# Super_LED_board.net
KiCad netlist of a schematic drawn in EAGLE
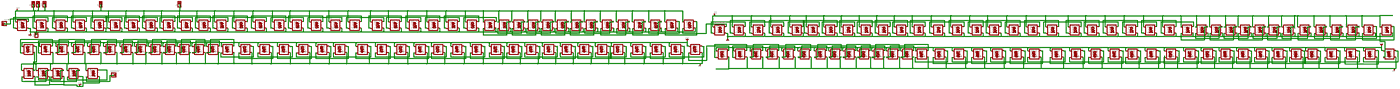
[diagram p0: schematic, sheet 1, overview]
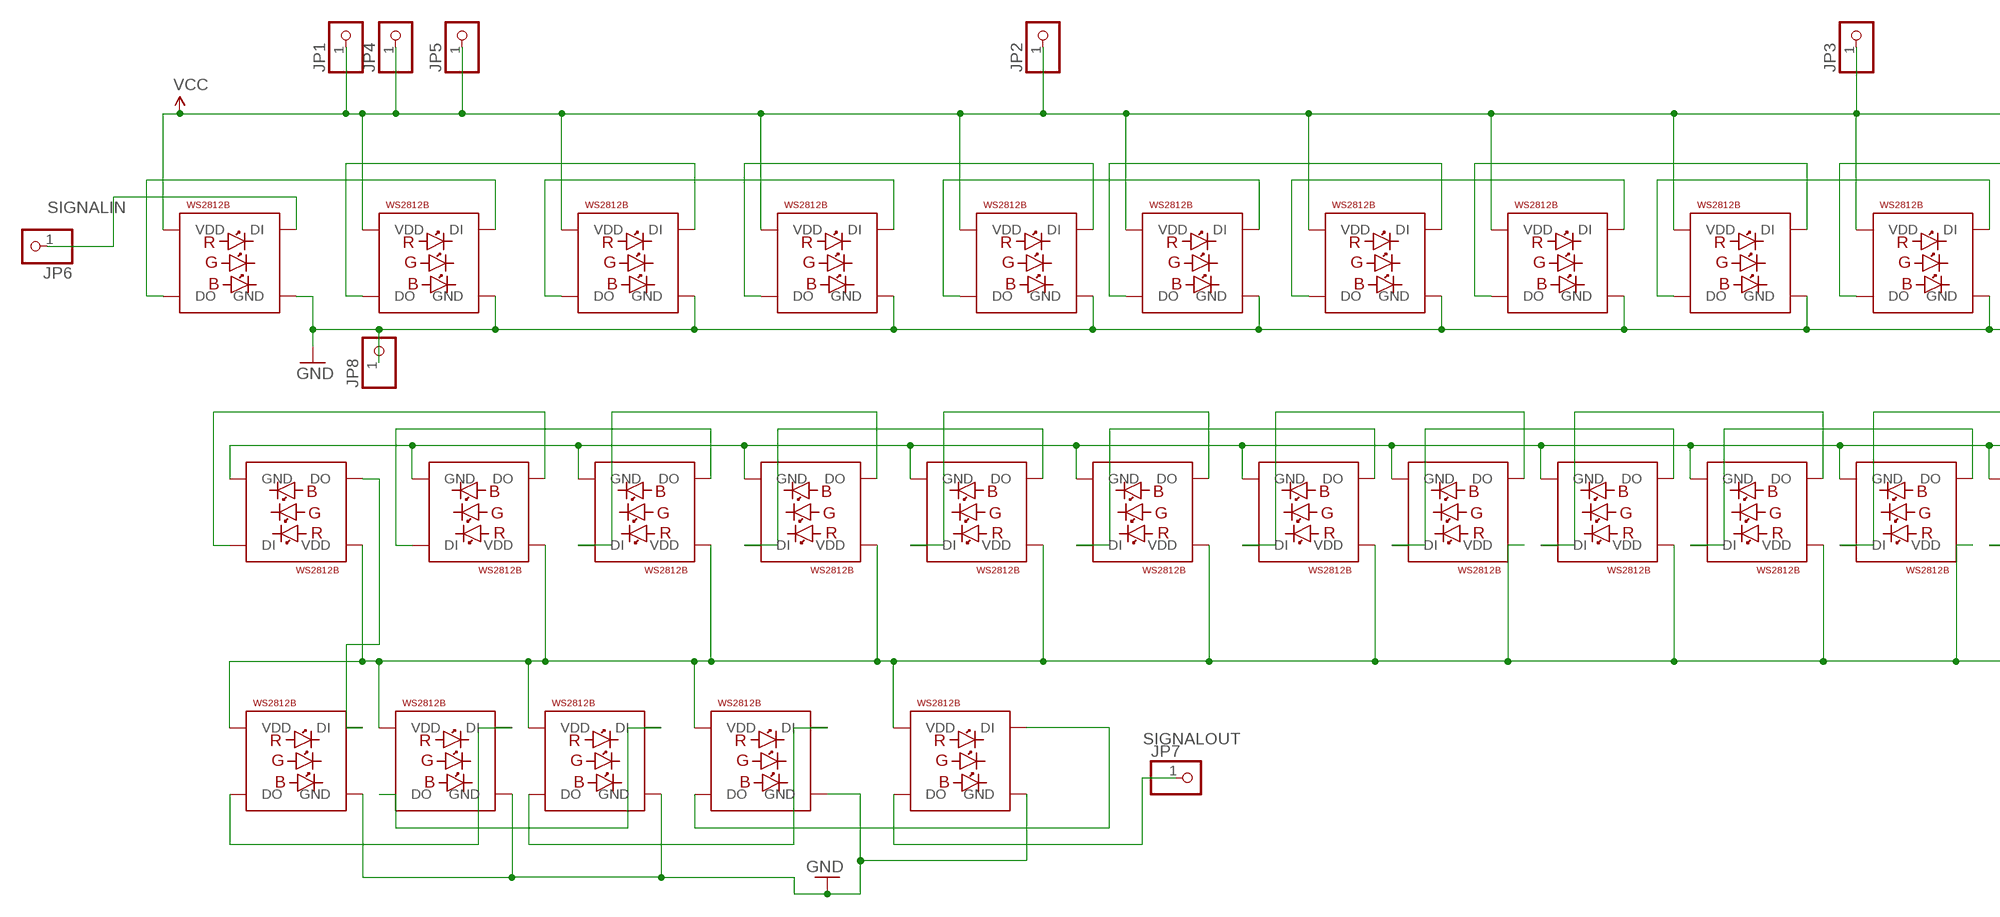
[diagram p1: schematic, sheet 1, part 1 of 8]
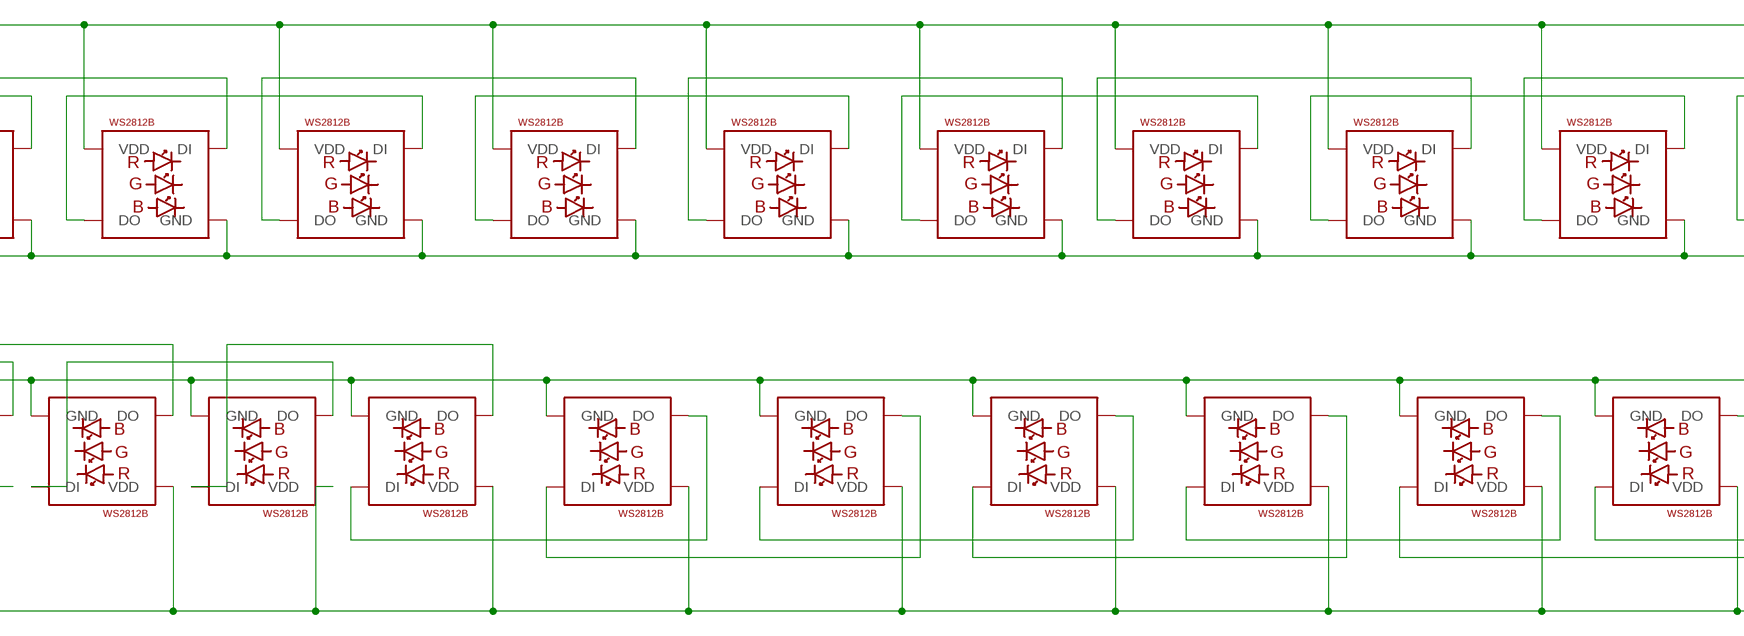
[diagram p2: schematic, sheet 1, part 2 of 8]
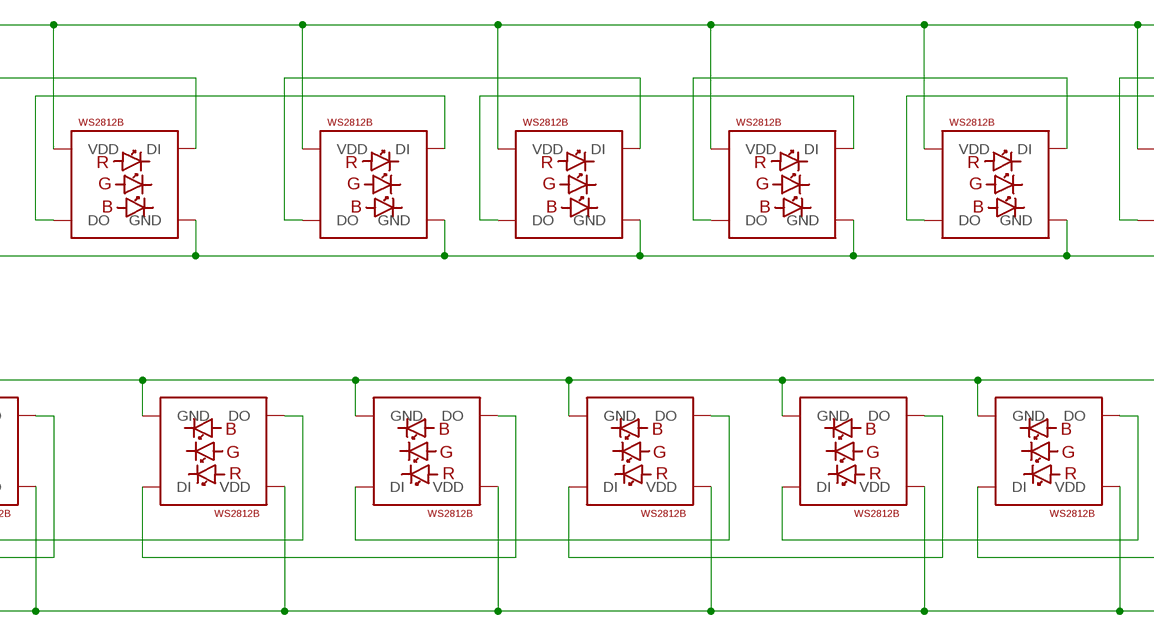
[diagram p3: schematic, sheet 1, part 3 of 8]
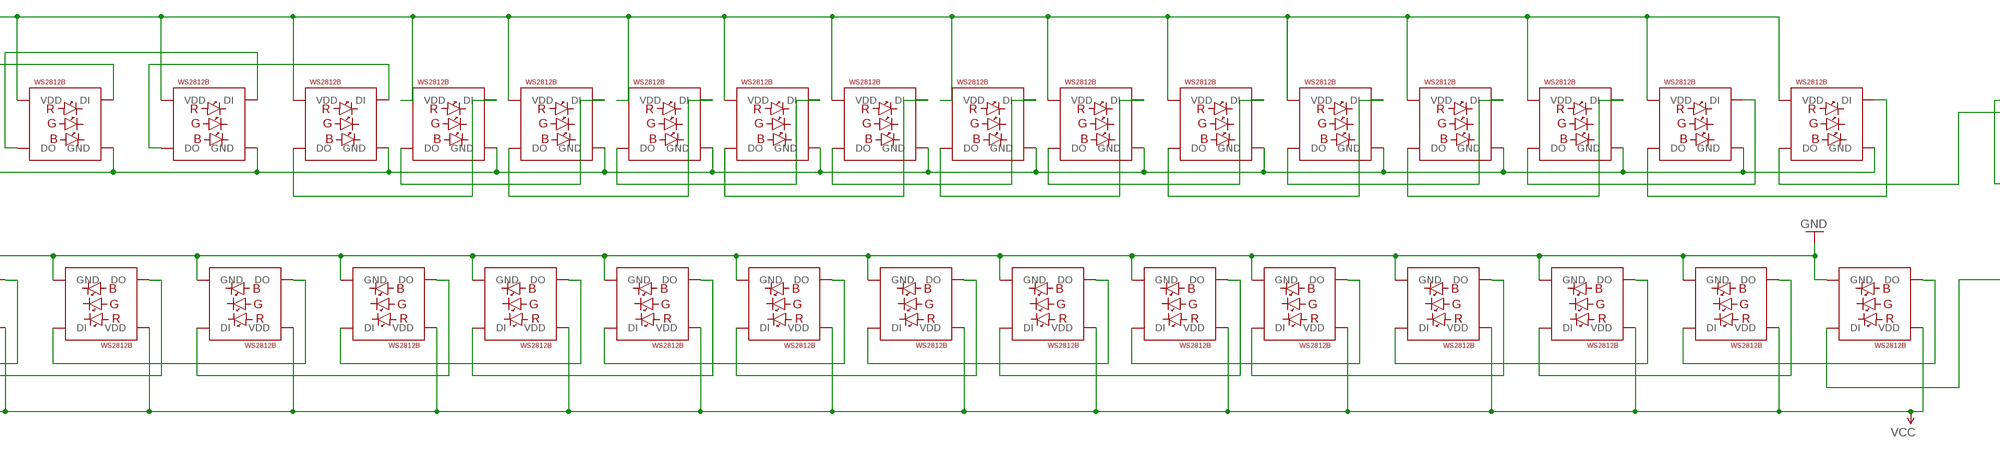
[diagram p4: schematic, sheet 1, part 4 of 8]
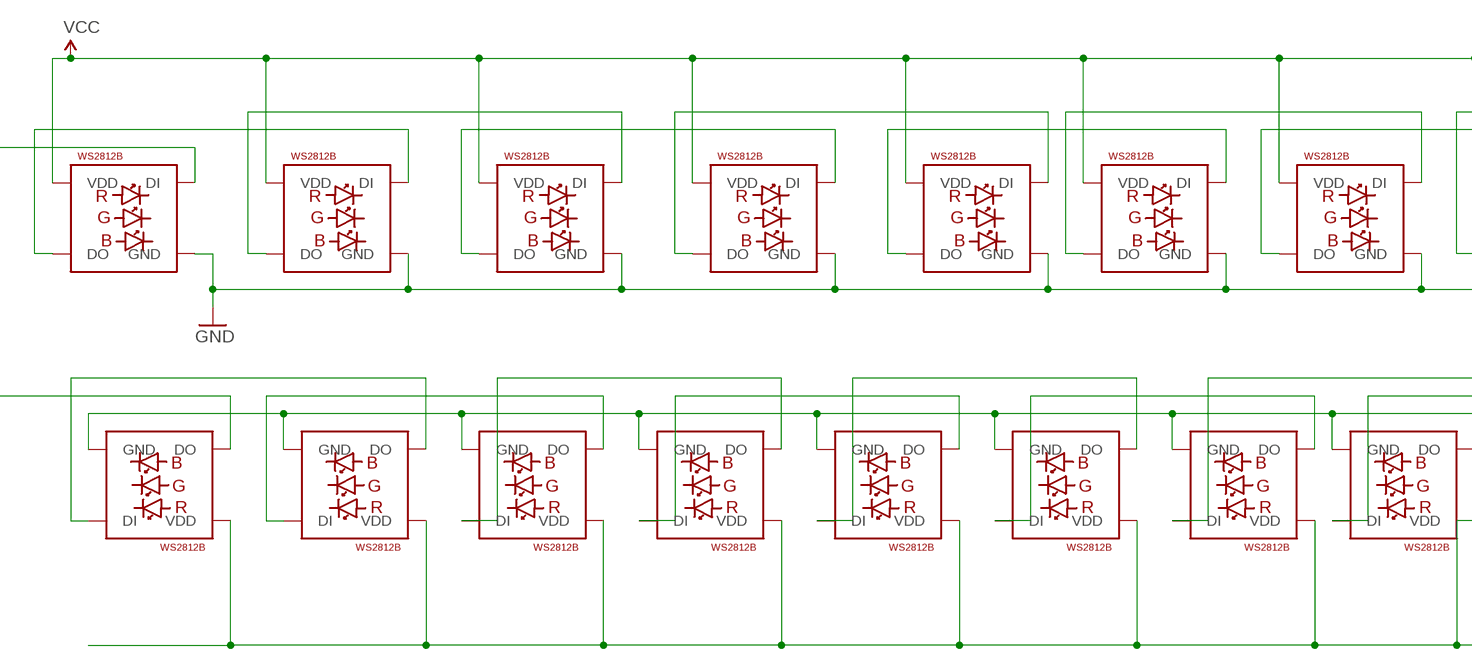
[diagram p5: schematic, sheet 1, part 5 of 8]
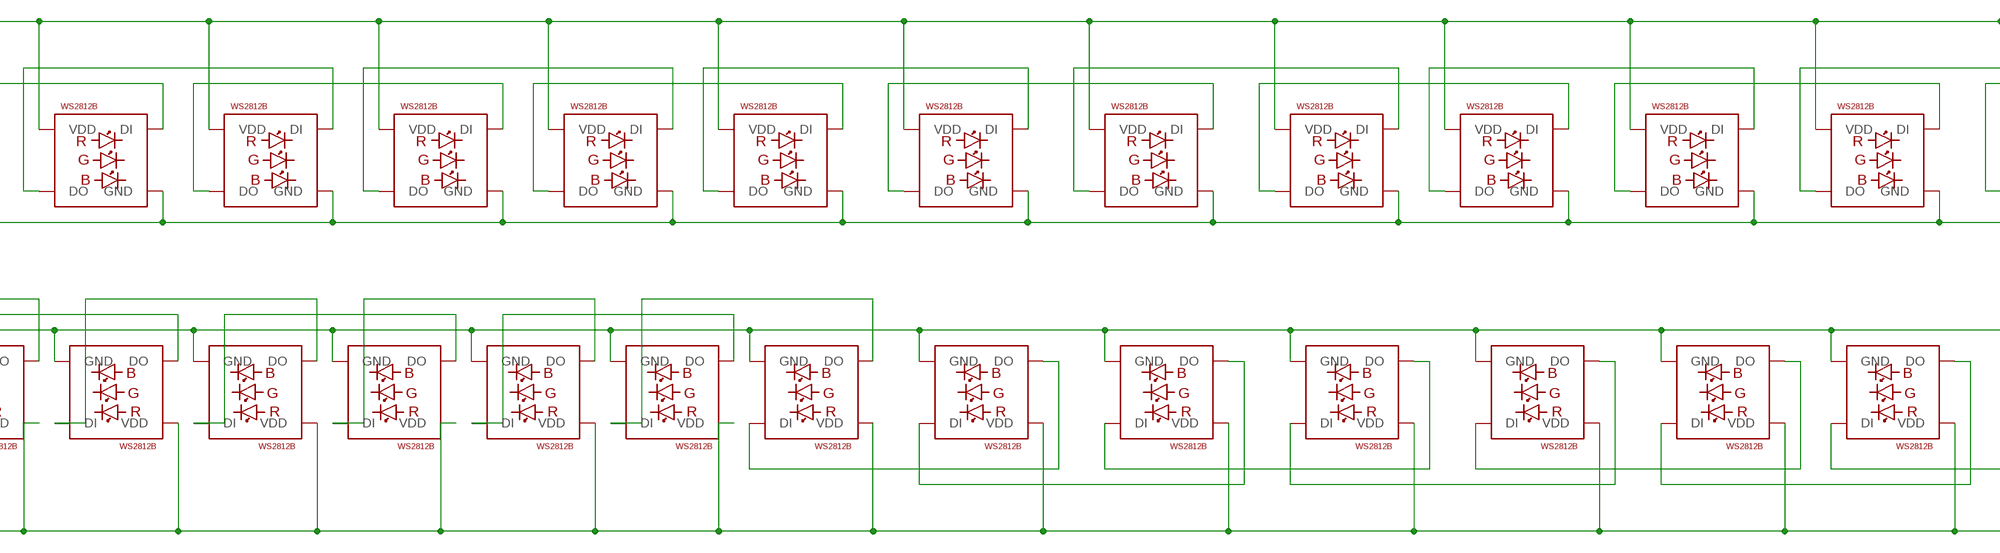
[diagram p6: schematic, sheet 1, part 6 of 8]
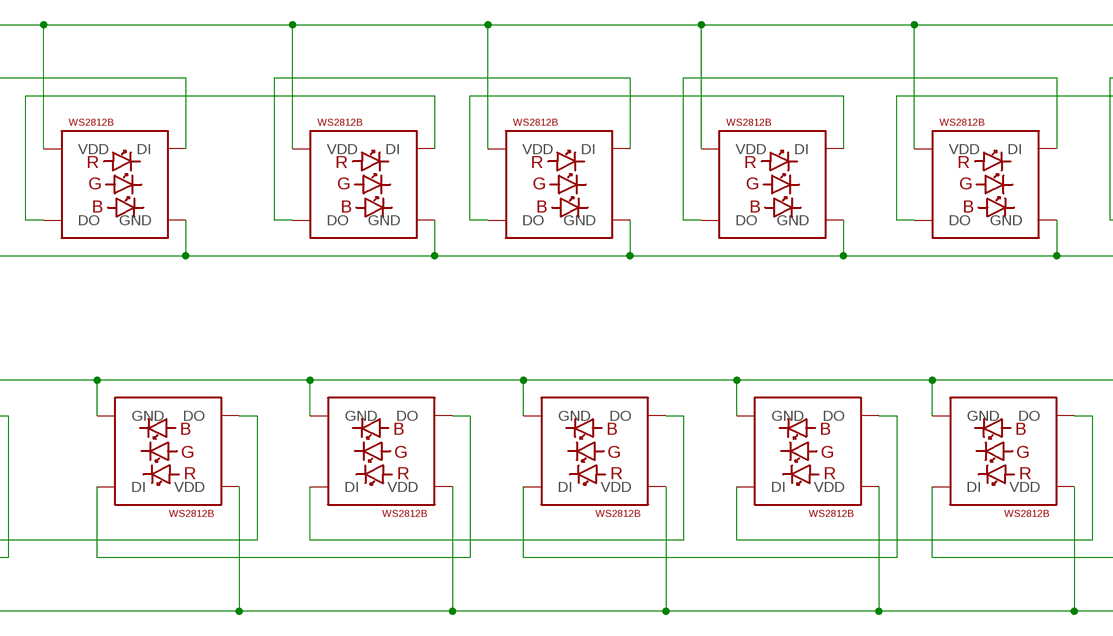
[diagram p7: schematic, sheet 1, part 7 of 8]
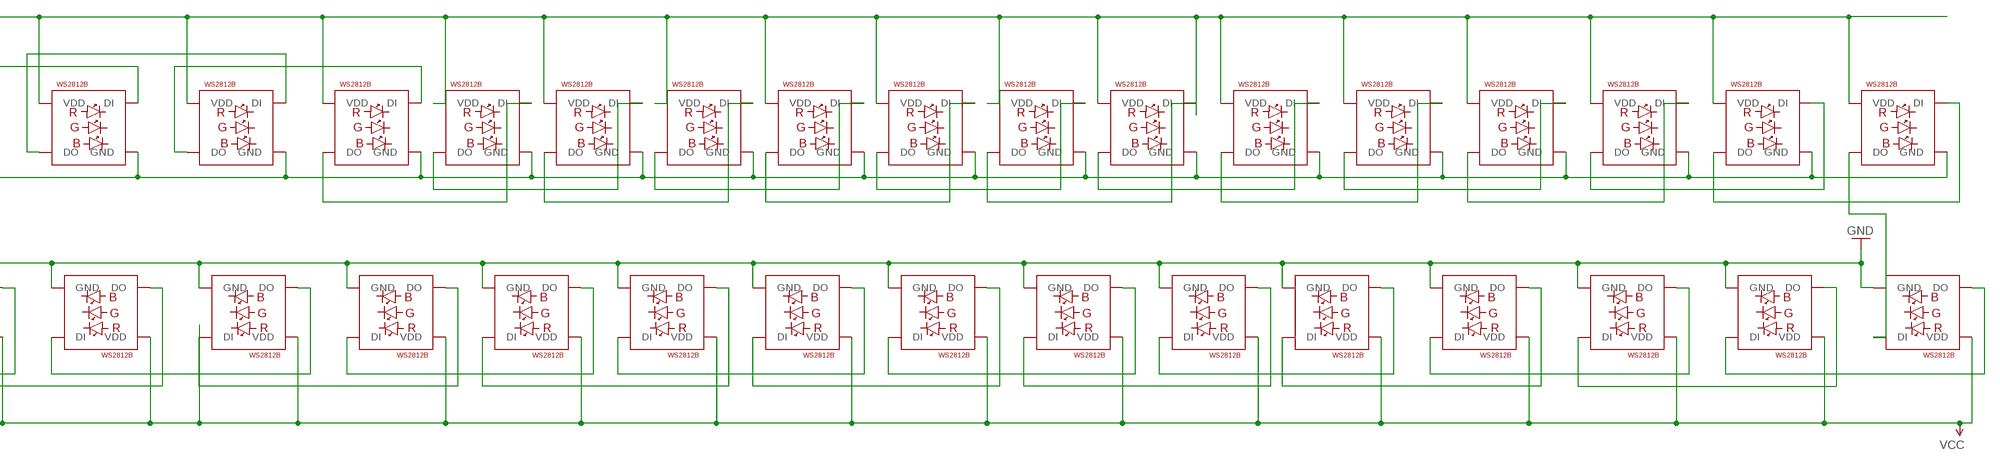
[diagram p8: schematic, sheet 1, part 8 of 8]

(export (version "E")
  (design (tool "Eeschema 10.0.6"))
  (components
    (comp (ref "JP1")
      (value "PINHD-1X1")
      (footprint "eagle-import:1X01")
      (libsource (lib "eagle-import") (part "PINHD-1X1"))
    )
    (comp (ref "JP2")
      (value "PINHD-1X1")
      (footprint "eagle-import:1X01")
      (libsource (lib "eagle-import") (part "PINHD-1X1"))
    )
    (comp (ref "JP3")
      (value "PINHD-1X1")
      (footprint "eagle-import:1X01")
      (libsource (lib "eagle-import") (part "PINHD-1X1"))
    )
    (comp (ref "JP4")
      (value "PINHD-1X1")
      (footprint "eagle-import:1X01")
      (libsource (lib "eagle-import") (part "PINHD-1X1"))
    )
    (comp (ref "JP5")
      (value "PINHD-1X1")
      (footprint "eagle-import:1X01")
      (libsource (lib "eagle-import") (part "PINHD-1X1"))
    )
    (comp (ref "JP6")
      (value "PINHD-1X1")
      (footprint "eagle-import:1X01")
      (libsource (lib "eagle-import") (part "PINHD-1X1"))
    )
    (comp (ref "JP7")
      (value "PINHD-1X1")
      (footprint "eagle-import:1X01")
      (libsource (lib "eagle-import") (part "PINHD-1X1"))
    )
    (comp (ref "JP8")
      (value "PINHD-1X1")
      (footprint "eagle-import:1X01")
      (libsource (lib "eagle-import") (part "PINHD-1X1"))
    )
    (comp (ref "LED1")
      (value "WS2812B5050")
      (footprint "eagle-import:WS2812B")
      (libsource (lib "eagle-import") (part "WS2812B5050"))
    )
    (comp (ref "LED2")
      (value "WS2812B5050")
      (footprint "eagle-import:WS2812B")
      (libsource (lib "eagle-import") (part "WS2812B5050"))
    )
    (comp (ref "LED3")
      (value "WS2812B5050")
      (footprint "eagle-import:WS2812B")
      (libsource (lib "eagle-import") (part "WS2812B5050"))
    )
    (comp (ref "LED4")
      (value "WS2812B5050")
      (footprint "eagle-import:WS2812B")
      (libsource (lib "eagle-import") (part "WS2812B5050"))
    )
    (comp (ref "LED5")
      (value "WS2812B5050")
      (footprint "eagle-import:WS2812B")
      (libsource (lib "eagle-import") (part "WS2812B5050"))
    )
    (comp (ref "LED6")
      (value "WS2812B5050")
      (footprint "eagle-import:WS2812B")
      (libsource (lib "eagle-import") (part "WS2812B5050"))
    )
    (comp (ref "LED7")
      (value "WS2812B5050")
      (footprint "eagle-import:WS2812B")
      (libsource (lib "eagle-import") (part "WS2812B5050"))
    )
    (comp (ref "LED8")
      (value "WS2812B5050")
      (footprint "eagle-import:WS2812B")
      (libsource (lib "eagle-import") (part "WS2812B5050"))
    )
    (comp (ref "LED9")
      (value "WS2812B5050")
      (footprint "eagle-import:WS2812B")
      (libsource (lib "eagle-import") (part "WS2812B5050"))
    )
    (comp (ref "LED10")
      (value "WS2812B5050")
      (footprint "eagle-import:WS2812B")
      (libsource (lib "eagle-import") (part "WS2812B5050"))
    )
    (comp (ref "LED11")
      (value "WS2812B5050")
      (footprint "eagle-import:WS2812B")
      (libsource (lib "eagle-import") (part "WS2812B5050"))
    )
    (comp (ref "LED12")
      (value "WS2812B5050")
      (footprint "eagle-import:WS2812B")
      (libsource (lib "eagle-import") (part "WS2812B5050"))
    )
    (comp (ref "LED13")
      (value "WS2812B5050")
      (footprint "eagle-import:WS2812B")
      (libsource (lib "eagle-import") (part "WS2812B5050"))
    )
    (comp (ref "LED14")
      (value "WS2812B5050")
      (footprint "eagle-import:WS2812B")
      (libsource (lib "eagle-import") (part "WS2812B5050"))
    )
    (comp (ref "LED15")
      (value "WS2812B5050")
      (footprint "eagle-import:WS2812B")
      (libsource (lib "eagle-import") (part "WS2812B5050"))
    )
    (comp (ref "LED16")
      (value "WS2812B5050")
      (footprint "eagle-import:WS2812B")
      (libsource (lib "eagle-import") (part "WS2812B5050"))
    )
    (comp (ref "LED17")
      (value "WS2812B5050")
      (footprint "eagle-import:WS2812B")
      (libsource (lib "eagle-import") (part "WS2812B5050"))
    )
    (comp (ref "LED18")
      (value "WS2812B5050")
      (footprint "eagle-import:WS2812B")
      (libsource (lib "eagle-import") (part "WS2812B5050"))
    )
    (comp (ref "LED19")
      (value "WS2812B5050")
      (footprint "eagle-import:WS2812B")
      (libsource (lib "eagle-import") (part "WS2812B5050"))
    )
    (comp (ref "LED20")
      (value "WS2812B5050")
      (footprint "eagle-import:WS2812B")
      (libsource (lib "eagle-import") (part "WS2812B5050"))
    )
    (comp (ref "LED21")
      (value "WS2812B5050")
      (footprint "eagle-import:WS2812B")
      (libsource (lib "eagle-import") (part "WS2812B5050"))
    )
    (comp (ref "LED22")
      (value "WS2812B5050")
      (footprint "eagle-import:WS2812B")
      (libsource (lib "eagle-import") (part "WS2812B5050"))
    )
    (comp (ref "LED23")
      (value "WS2812B5050")
      (footprint "eagle-import:WS2812B")
      (libsource (lib "eagle-import") (part "WS2812B5050"))
    )
    (comp (ref "LED24")
      (value "WS2812B5050")
      (footprint "eagle-import:WS2812B")
      (libsource (lib "eagle-import") (part "WS2812B5050"))
    )
    (comp (ref "LED25")
      (value "WS2812B5050")
      (footprint "eagle-import:WS2812B")
      (libsource (lib "eagle-import") (part "WS2812B5050"))
    )
    (comp (ref "LED26")
      (value "WS2812B5050")
      (footprint "eagle-import:WS2812B")
      (libsource (lib "eagle-import") (part "WS2812B5050"))
    )
    (comp (ref "LED27")
      (value "WS2812B5050")
      (footprint "eagle-import:WS2812B")
      (libsource (lib "eagle-import") (part "WS2812B5050"))
    )
    (comp (ref "LED28")
      (value "WS2812B5050")
      (footprint "eagle-import:WS2812B")
      (libsource (lib "eagle-import") (part "WS2812B5050"))
    )
    (comp (ref "LED29")
      (value "WS2812B5050")
      (footprint "eagle-import:WS2812B")
      (libsource (lib "eagle-import") (part "WS2812B5050"))
    )
    (comp (ref "LED30")
      (value "WS2812B5050")
      (footprint "eagle-import:WS2812B")
      (libsource (lib "eagle-import") (part "WS2812B5050"))
    )
    (comp (ref "LED31")
      (value "WS2812B5050")
      (footprint "eagle-import:WS2812B")
      (libsource (lib "eagle-import") (part "WS2812B5050"))
    )
    (comp (ref "LED32")
      (value "WS2812B5050")
      (footprint "eagle-import:WS2812B")
      (libsource (lib "eagle-import") (part "WS2812B5050"))
    )
    (comp (ref "LED33")
      (value "WS2812B5050")
      (footprint "eagle-import:WS2812B")
      (libsource (lib "eagle-import") (part "WS2812B5050"))
    )
    (comp (ref "LED34")
      (value "WS2812B5050")
      (footprint "eagle-import:WS2812B")
      (libsource (lib "eagle-import") (part "WS2812B5050"))
    )
    (comp (ref "LED35")
      (value "WS2812B5050")
      (footprint "eagle-import:WS2812B")
      (libsource (lib "eagle-import") (part "WS2812B5050"))
    )
    (comp (ref "LED36")
      (value "WS2812B5050")
      (footprint "eagle-import:WS2812B")
      (libsource (lib "eagle-import") (part "WS2812B5050"))
    )
    (comp (ref "LED37")
      (value "WS2812B5050")
      (footprint "eagle-import:WS2812B")
      (libsource (lib "eagle-import") (part "WS2812B5050"))
    )
    (comp (ref "LED38")
      (value "WS2812B5050")
      (footprint "eagle-import:WS2812B")
      (libsource (lib "eagle-import") (part "WS2812B5050"))
    )
    (comp (ref "LED39")
      (value "WS2812B5050")
      (footprint "eagle-import:WS2812B")
      (libsource (lib "eagle-import") (part "WS2812B5050"))
    )
    (comp (ref "LED40")
      (value "WS2812B5050")
      (footprint "eagle-import:WS2812B")
      (libsource (lib "eagle-import") (part "WS2812B5050"))
    )
    (comp (ref "LED41")
      (value "WS2812B5050")
      (footprint "eagle-import:WS2812B")
      (libsource (lib "eagle-import") (part "WS2812B5050"))
    )
    (comp (ref "LED42")
      (value "WS2812B5050")
      (footprint "eagle-import:WS2812B")
      (libsource (lib "eagle-import") (part "WS2812B5050"))
    )
    (comp (ref "LED43")
      (value "WS2812B5050")
      (footprint "eagle-import:WS2812B")
      (libsource (lib "eagle-import") (part "WS2812B5050"))
    )
    (comp (ref "LED44")
      (value "WS2812B5050")
      (footprint "eagle-import:WS2812B")
      (libsource (lib "eagle-import") (part "WS2812B5050"))
    )
    (comp (ref "LED45")
      (value "WS2812B5050")
      (footprint "eagle-import:WS2812B")
      (libsource (lib "eagle-import") (part "WS2812B5050"))
    )
    (comp (ref "LED46")
      (value "WS2812B5050")
      (footprint "eagle-import:WS2812B")
      (libsource (lib "eagle-import") (part "WS2812B5050"))
    )
    (comp (ref "LED47")
      (value "WS2812B5050")
      (footprint "eagle-import:WS2812B")
      (libsource (lib "eagle-import") (part "WS2812B5050"))
    )
    (comp (ref "LED48")
      (value "WS2812B5050")
      (footprint "eagle-import:WS2812B")
      (libsource (lib "eagle-import") (part "WS2812B5050"))
    )
    (comp (ref "LED49")
      (value "WS2812B5050")
      (footprint "eagle-import:WS2812B")
      (libsource (lib "eagle-import") (part "WS2812B5050"))
    )
    (comp (ref "LED50")
      (value "WS2812B5050")
      (footprint "eagle-import:WS2812B")
      (libsource (lib "eagle-import") (part "WS2812B5050"))
    )
    (comp (ref "LED51")
      (value "WS2812B5050")
      (footprint "eagle-import:WS2812B")
      (libsource (lib "eagle-import") (part "WS2812B5050"))
    )
    (comp (ref "LED52")
      (value "WS2812B5050")
      (footprint "eagle-import:WS2812B")
      (libsource (lib "eagle-import") (part "WS2812B5050"))
    )
    (comp (ref "LED53")
      (value "WS2812B5050")
      (footprint "eagle-import:WS2812B")
      (libsource (lib "eagle-import") (part "WS2812B5050"))
    )
    (comp (ref "LED54")
      (value "WS2812B5050")
      (footprint "eagle-import:WS2812B")
      (libsource (lib "eagle-import") (part "WS2812B5050"))
    )
    (comp (ref "LED55")
      (value "WS2812B5050")
      (footprint "eagle-import:WS2812B")
      (libsource (lib "eagle-import") (part "WS2812B5050"))
    )
    (comp (ref "LED56")
      (value "WS2812B5050")
      (footprint "eagle-import:WS2812B")
      (libsource (lib "eagle-import") (part "WS2812B5050"))
    )
    (comp (ref "LED57")
      (value "WS2812B5050")
      (footprint "eagle-import:WS2812B")
      (libsource (lib "eagle-import") (part "WS2812B5050"))
    )
    (comp (ref "LED58")
      (value "WS2812B5050")
      (footprint "eagle-import:WS2812B")
      (libsource (lib "eagle-import") (part "WS2812B5050"))
    )
    (comp (ref "LED59")
      (value "WS2812B5050")
      (footprint "eagle-import:WS2812B")
      (libsource (lib "eagle-import") (part "WS2812B5050"))
    )
    (comp (ref "LED60")
      (value "WS2812B5050")
      (footprint "eagle-import:WS2812B")
      (libsource (lib "eagle-import") (part "WS2812B5050"))
    )
    (comp (ref "LED61")
      (value "WS2812B5050")
      (footprint "eagle-import:WS2812B")
      (libsource (lib "eagle-import") (part "WS2812B5050"))
    )
    (comp (ref "LED62")
      (value "WS2812B5050")
      (footprint "eagle-import:WS2812B")
      (libsource (lib "eagle-import") (part "WS2812B5050"))
    )
    (comp (ref "LED63")
      (value "WS2812B5050")
      (footprint "eagle-import:WS2812B")
      (libsource (lib "eagle-import") (part "WS2812B5050"))
    )
    (comp (ref "LED64")
      (value "WS2812B5050")
      (footprint "eagle-import:WS2812B")
      (libsource (lib "eagle-import") (part "WS2812B5050"))
    )
    (comp (ref "LED65")
      (value "WS2812B5050")
      (footprint "eagle-import:WS2812B")
      (libsource (lib "eagle-import") (part "WS2812B5050"))
    )
    (comp (ref "LED66")
      (value "WS2812B5050")
      (footprint "eagle-import:WS2812B")
      (libsource (lib "eagle-import") (part "WS2812B5050"))
    )
    (comp (ref "LED67")
      (value "WS2812B5050")
      (footprint "eagle-import:WS2812B")
      (libsource (lib "eagle-import") (part "WS2812B5050"))
    )
    (comp (ref "LED68")
      (value "WS2812B5050")
      (footprint "eagle-import:WS2812B")
      (libsource (lib "eagle-import") (part "WS2812B5050"))
    )
    (comp (ref "LED69")
      (value "WS2812B5050")
      (footprint "eagle-import:WS2812B")
      (libsource (lib "eagle-import") (part "WS2812B5050"))
    )
    (comp (ref "LED70")
      (value "WS2812B5050")
      (footprint "eagle-import:WS2812B")
      (libsource (lib "eagle-import") (part "WS2812B5050"))
    )
    (comp (ref "LED71")
      (value "WS2812B5050")
      (footprint "eagle-import:WS2812B")
      (libsource (lib "eagle-import") (part "WS2812B5050"))
    )
    (comp (ref "LED72")
      (value "WS2812B5050")
      (footprint "eagle-import:WS2812B")
      (libsource (lib "eagle-import") (part "WS2812B5050"))
    )
    (comp (ref "LED73")
      (value "WS2812B5050")
      (footprint "eagle-import:WS2812B")
      (libsource (lib "eagle-import") (part "WS2812B5050"))
    )
    (comp (ref "LED74")
      (value "WS2812B5050")
      (footprint "eagle-import:WS2812B")
      (libsource (lib "eagle-import") (part "WS2812B5050"))
    )
    (comp (ref "LED75")
      (value "WS2812B5050")
      (footprint "eagle-import:WS2812B")
      (libsource (lib "eagle-import") (part "WS2812B5050"))
    )
    (comp (ref "LED76")
      (value "WS2812B5050")
      (footprint "eagle-import:WS2812B")
      (libsource (lib "eagle-import") (part "WS2812B5050"))
    )
    (comp (ref "LED77")
      (value "WS2812B5050")
      (footprint "eagle-import:WS2812B")
      (libsource (lib "eagle-import") (part "WS2812B5050"))
    )
    (comp (ref "LED78")
      (value "WS2812B5050")
      (footprint "eagle-import:WS2812B")
      (libsource (lib "eagle-import") (part "WS2812B5050"))
    )
    (comp (ref "LED79")
      (value "WS2812B5050")
      (footprint "eagle-import:WS2812B")
      (libsource (lib "eagle-import") (part "WS2812B5050"))
    )
    (comp (ref "LED80")
      (value "WS2812B5050")
      (footprint "eagle-import:WS2812B")
      (libsource (lib "eagle-import") (part "WS2812B5050"))
    )
    (comp (ref "LED81")
      (value "WS2812B5050")
      (footprint "eagle-import:WS2812B")
      (libsource (lib "eagle-import") (part "WS2812B5050"))
    )
    (comp (ref "LED82")
      (value "WS2812B5050")
      (footprint "eagle-import:WS2812B")
      (libsource (lib "eagle-import") (part "WS2812B5050"))
    )
    (comp (ref "LED83")
      (value "WS2812B5050")
      (footprint "eagle-import:WS2812B")
      (libsource (lib "eagle-import") (part "WS2812B5050"))
    )
    (comp (ref "LED84")
      (value "WS2812B5050")
      (footprint "eagle-import:WS2812B")
      (libsource (lib "eagle-import") (part "WS2812B5050"))
    )
    (comp (ref "LED85")
      (value "WS2812B5050")
      (footprint "eagle-import:WS2812B")
      (libsource (lib "eagle-import") (part "WS2812B5050"))
    )
    (comp (ref "LED86")
      (value "WS2812B5050")
      (footprint "eagle-import:WS2812B")
      (libsource (lib "eagle-import") (part "WS2812B5050"))
    )
    (comp (ref "LED87")
      (value "WS2812B5050")
      (footprint "eagle-import:WS2812B")
      (libsource (lib "eagle-import") (part "WS2812B5050"))
    )
    (comp (ref "LED88")
      (value "WS2812B5050")
      (footprint "eagle-import:WS2812B")
      (libsource (lib "eagle-import") (part "WS2812B5050"))
    )
    (comp (ref "LED89")
      (value "WS2812B5050")
      (footprint "eagle-import:WS2812B")
      (libsource (lib "eagle-import") (part "WS2812B5050"))
    )
    (comp (ref "LED90")
      (value "WS2812B5050")
      (footprint "eagle-import:WS2812B")
      (libsource (lib "eagle-import") (part "WS2812B5050"))
    )
    (comp (ref "LED91")
      (value "WS2812B5050")
      (footprint "eagle-import:WS2812B")
      (libsource (lib "eagle-import") (part "WS2812B5050"))
    )
    (comp (ref "LED92")
      (value "WS2812B5050")
      (footprint "eagle-import:WS2812B")
      (libsource (lib "eagle-import") (part "WS2812B5050"))
    )
    (comp (ref "LED93")
      (value "WS2812B5050")
      (footprint "eagle-import:WS2812B")
      (libsource (lib "eagle-import") (part "WS2812B5050"))
    )
    (comp (ref "LED94")
      (value "WS2812B5050")
      (footprint "eagle-import:WS2812B")
      (libsource (lib "eagle-import") (part "WS2812B5050"))
    )
    (comp (ref "LED95")
      (value "WS2812B5050")
      (footprint "eagle-import:WS2812B")
      (libsource (lib "eagle-import") (part "WS2812B5050"))
    )
    (comp (ref "LED96")
      (value "WS2812B5050")
      (footprint "eagle-import:WS2812B")
      (libsource (lib "eagle-import") (part "WS2812B5050"))
    )
    (comp (ref "LED97")
      (value "WS2812B5050")
      (footprint "eagle-import:WS2812B")
      (libsource (lib "eagle-import") (part "WS2812B5050"))
    )
    (comp (ref "LED98")
      (value "WS2812B5050")
      (footprint "eagle-import:WS2812B")
      (libsource (lib "eagle-import") (part "WS2812B5050"))
    )
    (comp (ref "LED99")
      (value "WS2812B5050")
      (footprint "eagle-import:WS2812B")
      (libsource (lib "eagle-import") (part "WS2812B5050"))
    )
    (comp (ref "LED100")
      (value "WS2812B5050")
      (footprint "eagle-import:WS2812B")
      (libsource (lib "eagle-import") (part "WS2812B5050"))
    )
    (comp (ref "LED101")
      (value "WS2812B5050")
      (footprint "eagle-import:WS2812B")
      (libsource (lib "eagle-import") (part "WS2812B5050"))
    )
    (comp (ref "LED102")
      (value "WS2812B5050")
      (footprint "eagle-import:WS2812B")
      (libsource (lib "eagle-import") (part "WS2812B5050"))
    )
    (comp (ref "LED103")
      (value "WS2812B5050")
      (footprint "eagle-import:WS2812B")
      (libsource (lib "eagle-import") (part "WS2812B5050"))
    )
    (comp (ref "LED104")
      (value "WS2812B5050")
      (footprint "eagle-import:WS2812B")
      (libsource (lib "eagle-import") (part "WS2812B5050"))
    )
    (comp (ref "LED105")
      (value "WS2812B5050")
      (footprint "eagle-import:WS2812B")
      (libsource (lib "eagle-import") (part "WS2812B5050"))
    )
    (comp (ref "LED106")
      (value "WS2812B5050")
      (footprint "eagle-import:WS2812B")
      (libsource (lib "eagle-import") (part "WS2812B5050"))
    )
    (comp (ref "LED107")
      (value "WS2812B5050")
      (footprint "eagle-import:WS2812B")
      (libsource (lib "eagle-import") (part "WS2812B5050"))
    )
    (comp (ref "LED108")
      (value "WS2812B5050")
      (footprint "eagle-import:WS2812B")
      (libsource (lib "eagle-import") (part "WS2812B5050"))
    )
    (comp (ref "LED109")
      (value "WS2812B5050")
      (footprint "eagle-import:WS2812B")
      (libsource (lib "eagle-import") (part "WS2812B5050"))
    )
    (comp (ref "LED110")
      (value "WS2812B5050")
      (footprint "eagle-import:WS2812B")
      (libsource (lib "eagle-import") (part "WS2812B5050"))
    )
    (comp (ref "LED111")
      (value "WS2812B5050")
      (footprint "eagle-import:WS2812B")
      (libsource (lib "eagle-import") (part "WS2812B5050"))
    )
    (comp (ref "LED112")
      (value "WS2812B5050")
      (footprint "eagle-import:WS2812B")
      (libsource (lib "eagle-import") (part "WS2812B5050"))
    )
    (comp (ref "LED113")
      (value "WS2812B5050")
      (footprint "eagle-import:WS2812B")
      (libsource (lib "eagle-import") (part "WS2812B5050"))
    )
    (comp (ref "LED114")
      (value "WS2812B5050")
      (footprint "eagle-import:WS2812B")
      (libsource (lib "eagle-import") (part "WS2812B5050"))
    )
    (comp (ref "LED115")
      (value "WS2812B5050")
      (footprint "eagle-import:WS2812B")
      (libsource (lib "eagle-import") (part "WS2812B5050"))
    )
    (comp (ref "LED116")
      (value "WS2812B5050")
      (footprint "eagle-import:WS2812B")
      (libsource (lib "eagle-import") (part "WS2812B5050"))
    )
    (comp (ref "LED117")
      (value "WS2812B5050")
      (footprint "eagle-import:WS2812B")
      (libsource (lib "eagle-import") (part "WS2812B5050"))
    )
    (comp (ref "LED118")
      (value "WS2812B5050")
      (footprint "eagle-import:WS2812B")
      (libsource (lib "eagle-import") (part "WS2812B5050"))
    )
    (comp (ref "LED119")
      (value "WS2812B5050")
      (footprint "eagle-import:WS2812B")
      (libsource (lib "eagle-import") (part "WS2812B5050"))
    )
    (comp (ref "LED120")
      (value "WS2812B5050")
      (footprint "eagle-import:WS2812B")
      (libsource (lib "eagle-import") (part "WS2812B5050"))
    )
    (comp (ref "LED121")
      (value "WS2812B5050")
      (footprint "eagle-import:WS2812B")
      (libsource (lib "eagle-import") (part "WS2812B5050"))
    )
    (comp (ref "LED122")
      (value "WS2812B5050")
      (footprint "eagle-import:WS2812B")
      (libsource (lib "eagle-import") (part "WS2812B5050"))
    )
    (comp (ref "LED123")
      (value "WS2812B5050")
      (footprint "eagle-import:WS2812B")
      (libsource (lib "eagle-import") (part "WS2812B5050"))
    )
    (comp (ref "LED124")
      (value "WS2812B5050")
      (footprint "eagle-import:WS2812B")
      (libsource (lib "eagle-import") (part "WS2812B5050"))
    )
    (comp (ref "LED125")
      (value "WS2812B5050")
      (footprint "eagle-import:WS2812B")
      (libsource (lib "eagle-import") (part "WS2812B5050"))
    )
    (comp (ref "LED126")
      (value "WS2812B5050")
      (footprint "eagle-import:WS2812B")
      (libsource (lib "eagle-import") (part "WS2812B5050"))
    )
    (comp (ref "LED127")
      (value "WS2812B5050")
      (footprint "eagle-import:WS2812B")
      (libsource (lib "eagle-import") (part "WS2812B5050"))
    )
    (comp (ref "LED128")
      (value "WS2812B5050")
      (footprint "eagle-import:WS2812B")
      (libsource (lib "eagle-import") (part "WS2812B5050"))
    )
    (comp (ref "LED129")
      (value "WS2812B5050")
      (footprint "eagle-import:WS2812B")
      (libsource (lib "eagle-import") (part "WS2812B5050"))
    )
    (comp (ref "LED130")
      (value "WS2812B5050")
      (footprint "eagle-import:WS2812B")
      (libsource (lib "eagle-import") (part "WS2812B5050"))
    )
    (comp (ref "LED131")
      (value "WS2812B5050")
      (footprint "eagle-import:WS2812B")
      (libsource (lib "eagle-import") (part "WS2812B5050"))
    )
    (comp (ref "LED132")
      (value "WS2812B5050")
      (footprint "eagle-import:WS2812B")
      (libsource (lib "eagle-import") (part "WS2812B5050"))
    )
    (comp (ref "LED133")
      (value "WS2812B5050")
      (footprint "eagle-import:WS2812B")
      (libsource (lib "eagle-import") (part "WS2812B5050"))
    )
    (comp (ref "LED134")
      (value "WS2812B5050")
      (footprint "eagle-import:WS2812B")
      (libsource (lib "eagle-import") (part "WS2812B5050"))
    )
    (comp (ref "LED135")
      (value "WS2812B5050")
      (footprint "eagle-import:WS2812B")
      (libsource (lib "eagle-import") (part "WS2812B5050"))
    )
    (comp (ref "LED136")
      (value "WS2812B5050")
      (footprint "eagle-import:WS2812B")
      (libsource (lib "eagle-import") (part "WS2812B5050"))
    )
    (comp (ref "LED137")
      (value "WS2812B5050")
      (footprint "eagle-import:WS2812B")
      (libsource (lib "eagle-import") (part "WS2812B5050"))
    )
    (comp (ref "LED138")
      (value "WS2812B5050")
      (footprint "eagle-import:WS2812B")
      (libsource (lib "eagle-import") (part "WS2812B5050"))
    )
    (comp (ref "LED139")
      (value "WS2812B5050")
      (footprint "eagle-import:WS2812B")
      (libsource (lib "eagle-import") (part "WS2812B5050"))
    )
    (comp (ref "LED140")
      (value "WS2812B5050")
      (footprint "eagle-import:WS2812B")
      (libsource (lib "eagle-import") (part "WS2812B5050"))
    )
    (comp (ref "LED141")
      (value "WS2812B5050")
      (footprint "eagle-import:WS2812B")
      (libsource (lib "eagle-import") (part "WS2812B5050"))
    )
    (comp (ref "LED142")
      (value "WS2812B5050")
      (footprint "eagle-import:WS2812B")
      (libsource (lib "eagle-import") (part "WS2812B5050"))
    )
    (comp (ref "LED143")
      (value "WS2812B5050")
      (footprint "eagle-import:WS2812B")
      (libsource (lib "eagle-import") (part "WS2812B5050"))
    )
    (comp (ref "LED144")
      (value "WS2812B5050")
      (footprint "eagle-import:WS2812B")
      (libsource (lib "eagle-import") (part "WS2812B5050"))
    )
    (comp (ref "LED145")
      (value "WS2812B5050")
      (footprint "eagle-import:WS2812B")
      (libsource (lib "eagle-import") (part "WS2812B5050"))
    )
    (comp (ref "LED146")
      (value "WS2812B5050")
      (footprint "eagle-import:WS2812B")
      (libsource (lib "eagle-import") (part "WS2812B5050"))
    )
    (comp (ref "LED147")
      (value "WS2812B5050")
      (footprint "eagle-import:WS2812B")
      (libsource (lib "eagle-import") (part "WS2812B5050"))
    )
    (comp (ref "LED148")
      (value "WS2812B5050")
      (footprint "eagle-import:WS2812B")
      (libsource (lib "eagle-import") (part "WS2812B5050"))
    )
    (comp (ref "LED149")
      (value "WS2812B5050")
      (footprint "eagle-import:WS2812B")
      (libsource (lib "eagle-import") (part "WS2812B5050"))
    )
    (comp (ref "LED150")
      (value "WS2812B5050")
      (footprint "eagle-import:WS2812B")
      (libsource (lib "eagle-import") (part "WS2812B5050"))
    )
    (comp (ref "LED151")
      (value "WS2812B5050")
      (footprint "eagle-import:WS2812B")
      (libsource (lib "eagle-import") (part "WS2812B5050"))
    )
    (comp (ref "LED152")
      (value "WS2812B5050")
      (footprint "eagle-import:WS2812B")
      (libsource (lib "eagle-import") (part "WS2812B5050"))
    )
    (comp (ref "LED153")
      (value "WS2812B5050")
      (footprint "eagle-import:WS2812B")
      (libsource (lib "eagle-import") (part "WS2812B5050"))
    )
    (comp (ref "LED154")
      (value "WS2812B5050")
      (footprint "eagle-import:WS2812B")
      (libsource (lib "eagle-import") (part "WS2812B5050"))
    )
    (comp (ref "LED155")
      (value "WS2812B5050")
      (footprint "eagle-import:WS2812B")
      (libsource (lib "eagle-import") (part "WS2812B5050"))
    )
    (comp (ref "LED156")
      (value "WS2812B5050")
      (footprint "eagle-import:WS2812B")
      (libsource (lib "eagle-import") (part "WS2812B5050"))
    )
    (comp (ref "LED157")
      (value "WS2812B5050")
      (footprint "eagle-import:WS2812B")
      (libsource (lib "eagle-import") (part "WS2812B5050"))
    )
    (comp (ref "LED158")
      (value "WS2812B5050")
      (footprint "eagle-import:WS2812B")
      (libsource (lib "eagle-import") (part "WS2812B5050"))
    )
    (comp (ref "LED159")
      (value "WS2812B5050")
      (footprint "eagle-import:WS2812B")
      (libsource (lib "eagle-import") (part "WS2812B5050"))
    )
    (comp (ref "LED160")
      (value "WS2812B5050")
      (footprint "eagle-import:WS2812B")
      (libsource (lib "eagle-import") (part "WS2812B5050"))
    )
    (comp (ref "LED161")
      (value "WS2812B5050")
      (footprint "eagle-import:WS2812B")
      (libsource (lib "eagle-import") (part "WS2812B5050"))
    )
  )
  (nets
    (net (code "1") (name "/SIGNALIN") (class "Default")
      (node (ref "JP6") (pin "1") (pinfunction "1_1") (pintype "passive"))
      (node (ref "LED1") (pin "4-DIN") (pinfunction "DI_4-DIN") (pintype "input"))
    )
    (net (code "2") (name "/SIGNALOUT") (class "Default")
      (node (ref "JP7") (pin "1") (pinfunction "1_1") (pintype "passive"))
      (node (ref "LED161") (pin "2-DOUT") (pinfunction "DO_2-DOUT") (pintype "output"))
    )
    (net (code "3") (name "GND") (class "Default")
      (node (ref "JP8") (pin "1") (pinfunction "1_1") (pintype "passive"))
      (node (ref "LED1") (pin "3-GND") (pinfunction "GND_3-GND") (pintype "power_in"))
      (node (ref "LED10") (pin "3-GND") (pinfunction "GND_3-GND") (pintype "power_in"))
      (node (ref "LED100") (pin "3-GND") (pinfunction "GND_3-GND") (pintype "power_in"))
      (node (ref "LED101") (pin "3-GND") (pinfunction "GND_3-GND") (pintype "power_in"))
      (node (ref "LED102") (pin "3-GND") (pinfunction "GND_3-GND") (pintype "power_in"))
      (node (ref "LED103") (pin "3-GND") (pinfunction "GND_3-GND") (pintype "power_in"))
      (node (ref "LED104") (pin "3-GND") (pinfunction "GND_3-GND") (pintype "power_in"))
      (node (ref "LED105") (pin "3-GND") (pinfunction "GND_3-GND") (pintype "power_in"))
      (node (ref "LED106") (pin "3-GND") (pinfunction "GND_3-GND") (pintype "power_in"))
      (node (ref "LED107") (pin "3-GND") (pinfunction "GND_3-GND") (pintype "power_in"))
      (node (ref "LED108") (pin "3-GND") (pinfunction "GND_3-GND") (pintype "power_in"))
      (node (ref "LED109") (pin "3-GND") (pinfunction "GND_3-GND") (pintype "power_in"))
      (node (ref "LED11") (pin "3-GND") (pinfunction "GND_3-GND") (pintype "power_in"))
      (node (ref "LED110") (pin "3-GND") (pinfunction "GND_3-GND") (pintype "power_in"))
      (node (ref "LED111") (pin "3-GND") (pinfunction "GND_3-GND") (pintype "power_in"))
      (node (ref "LED112") (pin "3-GND") (pinfunction "GND_3-GND") (pintype "power_in"))
      (node (ref "LED113") (pin "3-GND") (pinfunction "GND_3-GND") (pintype "power_in"))
      (node (ref "LED114") (pin "3-GND") (pinfunction "GND_3-GND") (pintype "power_in"))
      (node (ref "LED115") (pin "3-GND") (pinfunction "GND_3-GND") (pintype "power_in"))
      (node (ref "LED116") (pin "3-GND") (pinfunction "GND_3-GND") (pintype "power_in"))
      (node (ref "LED117") (pin "3-GND") (pinfunction "GND_3-GND") (pintype "power_in"))
      (node (ref "LED118") (pin "3-GND") (pinfunction "GND_3-GND") (pintype "power_in"))
      (node (ref "LED119") (pin "3-GND") (pinfunction "GND_3-GND") (pintype "power_in"))
      (node (ref "LED12") (pin "3-GND") (pinfunction "GND_3-GND") (pintype "power_in"))
      (node (ref "LED120") (pin "3-GND") (pinfunction "GND_3-GND") (pintype "power_in"))
      (node (ref "LED121") (pin "3-GND") (pinfunction "GND_3-GND") (pintype "power_in"))
      (node (ref "LED122") (pin "3-GND") (pinfunction "GND_3-GND") (pintype "power_in"))
      (node (ref "LED123") (pin "3-GND") (pinfunction "GND_3-GND") (pintype "power_in"))
      (node (ref "LED124") (pin "3-GND") (pinfunction "GND_3-GND") (pintype "power_in"))
      (node (ref "LED125") (pin "3-GND") (pinfunction "GND_3-GND") (pintype "power_in"))
      (node (ref "LED126") (pin "3-GND") (pinfunction "GND_3-GND") (pintype "power_in"))
      (node (ref "LED127") (pin "3-GND") (pinfunction "GND_3-GND") (pintype "power_in"))
      (node (ref "LED128") (pin "3-GND") (pinfunction "GND_3-GND") (pintype "power_in"))
      (node (ref "LED129") (pin "3-GND") (pinfunction "GND_3-GND") (pintype "power_in"))
      (node (ref "LED13") (pin "3-GND") (pinfunction "GND_3-GND") (pintype "power_in"))
      (node (ref "LED130") (pin "3-GND") (pinfunction "GND_3-GND") (pintype "power_in"))
      (node (ref "LED131") (pin "3-GND") (pinfunction "GND_3-GND") (pintype "power_in"))
      (node (ref "LED132") (pin "3-GND") (pinfunction "GND_3-GND") (pintype "power_in"))
      (node (ref "LED133") (pin "3-GND") (pinfunction "GND_3-GND") (pintype "power_in"))
      (node (ref "LED134") (pin "3-GND") (pinfunction "GND_3-GND") (pintype "power_in"))
      (node (ref "LED135") (pin "3-GND") (pinfunction "GND_3-GND") (pintype "power_in"))
      (node (ref "LED136") (pin "3-GND") (pinfunction "GND_3-GND") (pintype "power_in"))
      (node (ref "LED137") (pin "3-GND") (pinfunction "GND_3-GND") (pintype "power_in"))
      (node (ref "LED138") (pin "3-GND") (pinfunction "GND_3-GND") (pintype "power_in"))
      (node (ref "LED139") (pin "3-GND") (pinfunction "GND_3-GND") (pintype "power_in"))
      (node (ref "LED14") (pin "3-GND") (pinfunction "GND_3-GND") (pintype "power_in"))
      (node (ref "LED140") (pin "3-GND") (pinfunction "GND_3-GND") (pintype "power_in"))
      (node (ref "LED141") (pin "3-GND") (pinfunction "GND_3-GND") (pintype "power_in"))
      (node (ref "LED142") (pin "3-GND") (pinfunction "GND_3-GND") (pintype "power_in"))
      (node (ref "LED143") (pin "3-GND") (pinfunction "GND_3-GND") (pintype "power_in"))
      (node (ref "LED144") (pin "3-GND") (pinfunction "GND_3-GND") (pintype "power_in"))
      (node (ref "LED145") (pin "3-GND") (pinfunction "GND_3-GND") (pintype "power_in"))
      (node (ref "LED146") (pin "3-GND") (pinfunction "GND_3-GND") (pintype "power_in"))
      (node (ref "LED147") (pin "3-GND") (pinfunction "GND_3-GND") (pintype "power_in"))
      (node (ref "LED148") (pin "3-GND") (pinfunction "GND_3-GND") (pintype "power_in"))
      (node (ref "LED149") (pin "3-GND") (pinfunction "GND_3-GND") (pintype "power_in"))
      (node (ref "LED15") (pin "3-GND") (pinfunction "GND_3-GND") (pintype "power_in"))
      (node (ref "LED150") (pin "3-GND") (pinfunction "GND_3-GND") (pintype "power_in"))
      (node (ref "LED151") (pin "3-GND") (pinfunction "GND_3-GND") (pintype "power_in"))
      (node (ref "LED152") (pin "3-GND") (pinfunction "GND_3-GND") (pintype "power_in"))
      (node (ref "LED153") (pin "3-GND") (pinfunction "GND_3-GND") (pintype "power_in"))
      (node (ref "LED154") (pin "3-GND") (pinfunction "GND_3-GND") (pintype "power_in"))
      (node (ref "LED155") (pin "3-GND") (pinfunction "GND_3-GND") (pintype "power_in"))
      (node (ref "LED156") (pin "3-GND") (pinfunction "GND_3-GND") (pintype "power_in"))
      (node (ref "LED157") (pin "3-GND") (pinfunction "GND_3-GND") (pintype "power_in"))
      (node (ref "LED158") (pin "3-GND") (pinfunction "GND_3-GND") (pintype "power_in"))
      (node (ref "LED159") (pin "3-GND") (pinfunction "GND_3-GND") (pintype "power_in"))
      (node (ref "LED16") (pin "3-GND") (pinfunction "GND_3-GND") (pintype "power_in"))
      (node (ref "LED160") (pin "3-GND") (pinfunction "GND_3-GND") (pintype "power_in"))
      (node (ref "LED161") (pin "3-GND") (pinfunction "GND_3-GND") (pintype "power_in"))
      (node (ref "LED17") (pin "3-GND") (pinfunction "GND_3-GND") (pintype "power_in"))
      (node (ref "LED18") (pin "3-GND") (pinfunction "GND_3-GND") (pintype "power_in"))
      (node (ref "LED19") (pin "3-GND") (pinfunction "GND_3-GND") (pintype "power_in"))
      (node (ref "LED2") (pin "3-GND") (pinfunction "GND_3-GND") (pintype "power_in"))
      (node (ref "LED20") (pin "3-GND") (pinfunction "GND_3-GND") (pintype "power_in"))
      (node (ref "LED21") (pin "3-GND") (pinfunction "GND_3-GND") (pintype "power_in"))
      (node (ref "LED22") (pin "3-GND") (pinfunction "GND_3-GND") (pintype "power_in"))
      (node (ref "LED23") (pin "3-GND") (pinfunction "GND_3-GND") (pintype "power_in"))
      (node (ref "LED24") (pin "3-GND") (pinfunction "GND_3-GND") (pintype "power_in"))
      (node (ref "LED25") (pin "3-GND") (pinfunction "GND_3-GND") (pintype "power_in"))
      (node (ref "LED26") (pin "3-GND") (pinfunction "GND_3-GND") (pintype "power_in"))
      (node (ref "LED27") (pin "3-GND") (pinfunction "GND_3-GND") (pintype "power_in"))
      (node (ref "LED28") (pin "3-GND") (pinfunction "GND_3-GND") (pintype "power_in"))
      (node (ref "LED29") (pin "3-GND") (pinfunction "GND_3-GND") (pintype "power_in"))
      (node (ref "LED3") (pin "3-GND") (pinfunction "GND_3-GND") (pintype "power_in"))
      (node (ref "LED30") (pin "3-GND") (pinfunction "GND_3-GND") (pintype "power_in"))
      (node (ref "LED31") (pin "3-GND") (pinfunction "GND_3-GND") (pintype "power_in"))
      (node (ref "LED32") (pin "3-GND") (pinfunction "GND_3-GND") (pintype "power_in"))
      (node (ref "LED33") (pin "3-GND") (pinfunction "GND_3-GND") (pintype "power_in"))
      (node (ref "LED34") (pin "3-GND") (pinfunction "GND_3-GND") (pintype "power_in"))
      (node (ref "LED35") (pin "3-GND") (pinfunction "GND_3-GND") (pintype "power_in"))
      (node (ref "LED36") (pin "3-GND") (pinfunction "GND_3-GND") (pintype "power_in"))
      (node (ref "LED37") (pin "3-GND") (pinfunction "GND_3-GND") (pintype "power_in"))
      (node (ref "LED38") (pin "3-GND") (pinfunction "GND_3-GND") (pintype "power_in"))
      (node (ref "LED39") (pin "3-GND") (pinfunction "GND_3-GND") (pintype "power_in"))
      (node (ref "LED4") (pin "3-GND") (pinfunction "GND_3-GND") (pintype "power_in"))
      (node (ref "LED40") (pin "3-GND") (pinfunction "GND_3-GND") (pintype "power_in"))
      (node (ref "LED41") (pin "3-GND") (pinfunction "GND_3-GND") (pintype "power_in"))
      (node (ref "LED42") (pin "3-GND") (pinfunction "GND_3-GND") (pintype "power_in"))
      (node (ref "LED43") (pin "3-GND") (pinfunction "GND_3-GND") (pintype "power_in"))
      (node (ref "LED44") (pin "3-GND") (pinfunction "GND_3-GND") (pintype "power_in"))
      (node (ref "LED45") (pin "3-GND") (pinfunction "GND_3-GND") (pintype "power_in"))
      (node (ref "LED46") (pin "3-GND") (pinfunction "GND_3-GND") (pintype "power_in"))
      (node (ref "LED47") (pin "3-GND") (pinfunction "GND_3-GND") (pintype "power_in"))
      (node (ref "LED48") (pin "3-GND") (pinfunction "GND_3-GND") (pintype "power_in"))
      (node (ref "LED49") (pin "3-GND") (pinfunction "GND_3-GND") (pintype "power_in"))
      (node (ref "LED5") (pin "3-GND") (pinfunction "GND_3-GND") (pintype "power_in"))
      (node (ref "LED50") (pin "3-GND") (pinfunction "GND_3-GND") (pintype "power_in"))
      (node (ref "LED51") (pin "3-GND") (pinfunction "GND_3-GND") (pintype "power_in"))
      (node (ref "LED52") (pin "3-GND") (pinfunction "GND_3-GND") (pintype "power_in"))
      (node (ref "LED53") (pin "3-GND") (pinfunction "GND_3-GND") (pintype "power_in"))
      (node (ref "LED54") (pin "3-GND") (pinfunction "GND_3-GND") (pintype "power_in"))
      (node (ref "LED55") (pin "3-GND") (pinfunction "GND_3-GND") (pintype "power_in"))
      (node (ref "LED56") (pin "3-GND") (pinfunction "GND_3-GND") (pintype "power_in"))
      (node (ref "LED57") (pin "3-GND") (pinfunction "GND_3-GND") (pintype "power_in"))
      (node (ref "LED58") (pin "3-GND") (pinfunction "GND_3-GND") (pintype "power_in"))
      (node (ref "LED59") (pin "3-GND") (pinfunction "GND_3-GND") (pintype "power_in"))
      (node (ref "LED6") (pin "3-GND") (pinfunction "GND_3-GND") (pintype "power_in"))
      (node (ref "LED60") (pin "3-GND") (pinfunction "GND_3-GND") (pintype "power_in"))
      (node (ref "LED61") (pin "3-GND") (pinfunction "GND_3-GND") (pintype "power_in"))
      (node (ref "LED62") (pin "3-GND") (pinfunction "GND_3-GND") (pintype "power_in"))
      (node (ref "LED63") (pin "3-GND") (pinfunction "GND_3-GND") (pintype "power_in"))
      (node (ref "LED64") (pin "3-GND") (pinfunction "GND_3-GND") (pintype "power_in"))
      (node (ref "LED65") (pin "3-GND") (pinfunction "GND_3-GND") (pintype "power_in"))
      (node (ref "LED66") (pin "3-GND") (pinfunction "GND_3-GND") (pintype "power_in"))
      (node (ref "LED67") (pin "3-GND") (pinfunction "GND_3-GND") (pintype "power_in"))
      (node (ref "LED68") (pin "3-GND") (pinfunction "GND_3-GND") (pintype "power_in"))
      (node (ref "LED69") (pin "3-GND") (pinfunction "GND_3-GND") (pintype "power_in"))
      (node (ref "LED7") (pin "3-GND") (pinfunction "GND_3-GND") (pintype "power_in"))
      (node (ref "LED70") (pin "3-GND") (pinfunction "GND_3-GND") (pintype "power_in"))
      (node (ref "LED71") (pin "3-GND") (pinfunction "GND_3-GND") (pintype "power_in"))
      (node (ref "LED72") (pin "3-GND") (pinfunction "GND_3-GND") (pintype "power_in"))
      (node (ref "LED73") (pin "3-GND") (pinfunction "GND_3-GND") (pintype "power_in"))
      (node (ref "LED74") (pin "3-GND") (pinfunction "GND_3-GND") (pintype "power_in"))
      (node (ref "LED75") (pin "3-GND") (pinfunction "GND_3-GND") (pintype "power_in"))
      (node (ref "LED76") (pin "3-GND") (pinfunction "GND_3-GND") (pintype "power_in"))
      (node (ref "LED77") (pin "3-GND") (pinfunction "GND_3-GND") (pintype "power_in"))
      (node (ref "LED78") (pin "3-GND") (pinfunction "GND_3-GND") (pintype "power_in"))
      (node (ref "LED79") (pin "3-GND") (pinfunction "GND_3-GND") (pintype "power_in"))
      (node (ref "LED8") (pin "3-GND") (pinfunction "GND_3-GND") (pintype "power_in"))
      (node (ref "LED80") (pin "3-GND") (pinfunction "GND_3-GND") (pintype "power_in"))
      (node (ref "LED81") (pin "3-GND") (pinfunction "GND_3-GND") (pintype "power_in"))
      (node (ref "LED82") (pin "3-GND") (pinfunction "GND_3-GND") (pintype "power_in"))
      (node (ref "LED83") (pin "3-GND") (pinfunction "GND_3-GND") (pintype "power_in"))
      (node (ref "LED84") (pin "3-GND") (pinfunction "GND_3-GND") (pintype "power_in"))
      (node (ref "LED85") (pin "3-GND") (pinfunction "GND_3-GND") (pintype "power_in"))
      (node (ref "LED86") (pin "3-GND") (pinfunction "GND_3-GND") (pintype "power_in"))
      (node (ref "LED87") (pin "3-GND") (pinfunction "GND_3-GND") (pintype "power_in"))
      (node (ref "LED88") (pin "3-GND") (pinfunction "GND_3-GND") (pintype "power_in"))
      (node (ref "LED89") (pin "3-GND") (pinfunction "GND_3-GND") (pintype "power_in"))
      (node (ref "LED9") (pin "3-GND") (pinfunction "GND_3-GND") (pintype "power_in"))
      (node (ref "LED90") (pin "3-GND") (pinfunction "GND_3-GND") (pintype "power_in"))
      (node (ref "LED91") (pin "3-GND") (pinfunction "GND_3-GND") (pintype "power_in"))
      (node (ref "LED92") (pin "3-GND") (pinfunction "GND_3-GND") (pintype "power_in"))
      (node (ref "LED93") (pin "3-GND") (pinfunction "GND_3-GND") (pintype "power_in"))
      (node (ref "LED94") (pin "3-GND") (pinfunction "GND_3-GND") (pintype "power_in"))
      (node (ref "LED95") (pin "3-GND") (pinfunction "GND_3-GND") (pintype "power_in"))
      (node (ref "LED96") (pin "3-GND") (pinfunction "GND_3-GND") (pintype "power_in"))
      (node (ref "LED97") (pin "3-GND") (pinfunction "GND_3-GND") (pintype "power_in"))
      (node (ref "LED98") (pin "3-GND") (pinfunction "GND_3-GND") (pintype "power_in"))
      (node (ref "LED99") (pin "3-GND") (pinfunction "GND_3-GND") (pintype "power_in"))
    )
    (net (code "4") (name "Net-(LED1-DO)") (class "Default")
      (node (ref "LED1") (pin "2-DOUT") (pinfunction "DO_2-DOUT") (pintype "output"))
      (node (ref "LED2") (pin "4-DIN") (pinfunction "DI_4-DIN") (pintype "input"))
    )
    (net (code "5") (name "Net-(LED2-DO)") (class "Default")
      (node (ref "LED2") (pin "2-DOUT") (pinfunction "DO_2-DOUT") (pintype "output"))
      (node (ref "LED3") (pin "4-DIN") (pinfunction "DI_4-DIN") (pintype "input"))
    )
    (net (code "6") (name "Net-(LED3-DO)") (class "Default")
      (node (ref "LED3") (pin "2-DOUT") (pinfunction "DO_2-DOUT") (pintype "output"))
      (node (ref "LED4") (pin "4-DIN") (pinfunction "DI_4-DIN") (pintype "input"))
    )
    (net (code "7") (name "Net-(LED4-DO)") (class "Default")
      (node (ref "LED4") (pin "2-DOUT") (pinfunction "DO_2-DOUT") (pintype "output"))
      (node (ref "LED5") (pin "4-DIN") (pinfunction "DI_4-DIN") (pintype "input"))
    )
    (net (code "8") (name "Net-(LED5-DO)") (class "Default")
      (node (ref "LED5") (pin "2-DOUT") (pinfunction "DO_2-DOUT") (pintype "output"))
      (node (ref "LED6") (pin "4-DIN") (pinfunction "DI_4-DIN") (pintype "input"))
    )
    (net (code "9") (name "Net-(LED6-DO)") (class "Default")
      (node (ref "LED6") (pin "2-DOUT") (pinfunction "DO_2-DOUT") (pintype "output"))
      (node (ref "LED7") (pin "4-DIN") (pinfunction "DI_4-DIN") (pintype "input"))
    )
    (net (code "10") (name "Net-(LED7-DO)") (class "Default")
      (node (ref "LED7") (pin "2-DOUT") (pinfunction "DO_2-DOUT") (pintype "output"))
      (node (ref "LED8") (pin "4-DIN") (pinfunction "DI_4-DIN") (pintype "input"))
    )
    (net (code "11") (name "Net-(LED8-DO)") (class "Default")
      (node (ref "LED8") (pin "2-DOUT") (pinfunction "DO_2-DOUT") (pintype "output"))
      (node (ref "LED9") (pin "4-DIN") (pinfunction "DI_4-DIN") (pintype "input"))
    )
    (net (code "12") (name "Net-(LED10-DI)") (class "Default")
      (node (ref "LED10") (pin "4-DIN") (pinfunction "DI_4-DIN") (pintype "input"))
      (node (ref "LED9") (pin "2-DOUT") (pinfunction "DO_2-DOUT") (pintype "output"))
    )
    (net (code "13") (name "Net-(LED10-DO)") (class "Default")
      (node (ref "LED10") (pin "2-DOUT") (pinfunction "DO_2-DOUT") (pintype "output"))
      (node (ref "LED11") (pin "4-DIN") (pinfunction "DI_4-DIN") (pintype "input"))
    )
    (net (code "14") (name "Net-(LED11-DO)") (class "Default")
      (node (ref "LED11") (pin "2-DOUT") (pinfunction "DO_2-DOUT") (pintype "output"))
      (node (ref "LED12") (pin "4-DIN") (pinfunction "DI_4-DIN") (pintype "input"))
    )
    (net (code "15") (name "Net-(LED12-DO)") (class "Default")
      (node (ref "LED12") (pin "2-DOUT") (pinfunction "DO_2-DOUT") (pintype "output"))
      (node (ref "LED13") (pin "4-DIN") (pinfunction "DI_4-DIN") (pintype "input"))
    )
    (net (code "16") (name "Net-(LED13-DO)") (class "Default")
      (node (ref "LED13") (pin "2-DOUT") (pinfunction "DO_2-DOUT") (pintype "output"))
      (node (ref "LED14") (pin "4-DIN") (pinfunction "DI_4-DIN") (pintype "input"))
    )
    (net (code "17") (name "Net-(LED14-DO)") (class "Default")
      (node (ref "LED14") (pin "2-DOUT") (pinfunction "DO_2-DOUT") (pintype "output"))
      (node (ref "LED15") (pin "4-DIN") (pinfunction "DI_4-DIN") (pintype "input"))
    )
    (net (code "18") (name "Net-(LED15-DO)") (class "Default")
      (node (ref "LED15") (pin "2-DOUT") (pinfunction "DO_2-DOUT") (pintype "output"))
      (node (ref "LED16") (pin "4-DIN") (pinfunction "DI_4-DIN") (pintype "input"))
    )
    (net (code "19") (name "Net-(LED16-DO)") (class "Default")
      (node (ref "LED16") (pin "2-DOUT") (pinfunction "DO_2-DOUT") (pintype "output"))
      (node (ref "LED17") (pin "4-DIN") (pinfunction "DI_4-DIN") (pintype "input"))
    )
    (net (code "20") (name "Net-(LED17-DO)") (class "Default")
      (node (ref "LED17") (pin "2-DOUT") (pinfunction "DO_2-DOUT") (pintype "output"))
      (node (ref "LED18") (pin "4-DIN") (pinfunction "DI_4-DIN") (pintype "input"))
    )
    (net (code "21") (name "Net-(LED18-DO)") (class "Default")
      (node (ref "LED18") (pin "2-DOUT") (pinfunction "DO_2-DOUT") (pintype "output"))
      (node (ref "LED19") (pin "4-DIN") (pinfunction "DI_4-DIN") (pintype "input"))
    )
    (net (code "22") (name "Net-(LED19-DO)") (class "Default")
      (node (ref "LED19") (pin "2-DOUT") (pinfunction "DO_2-DOUT") (pintype "output"))
      (node (ref "LED20") (pin "4-DIN") (pinfunction "DI_4-DIN") (pintype "input"))
    )
    (net (code "23") (name "Net-(LED20-DO)") (class "Default")
      (node (ref "LED20") (pin "2-DOUT") (pinfunction "DO_2-DOUT") (pintype "output"))
      (node (ref "LED21") (pin "4-DIN") (pinfunction "DI_4-DIN") (pintype "input"))
    )
    (net (code "24") (name "Net-(LED21-DO)") (class "Default")
      (node (ref "LED21") (pin "2-DOUT") (pinfunction "DO_2-DOUT") (pintype "output"))
      (node (ref "LED22") (pin "4-DIN") (pinfunction "DI_4-DIN") (pintype "input"))
    )
    (net (code "25") (name "Net-(LED22-DO)") (class "Default")
      (node (ref "LED22") (pin "2-DOUT") (pinfunction "DO_2-DOUT") (pintype "output"))
      (node (ref "LED23") (pin "4-DIN") (pinfunction "DI_4-DIN") (pintype "input"))
    )
    (net (code "26") (name "Net-(LED23-DO)") (class "Default")
      (node (ref "LED23") (pin "2-DOUT") (pinfunction "DO_2-DOUT") (pintype "output"))
      (node (ref "LED24") (pin "4-DIN") (pinfunction "DI_4-DIN") (pintype "input"))
    )
    (net (code "27") (name "Net-(LED24-DO)") (class "Default")
      (node (ref "LED24") (pin "2-DOUT") (pinfunction "DO_2-DOUT") (pintype "output"))
      (node (ref "LED25") (pin "4-DIN") (pinfunction "DI_4-DIN") (pintype "input"))
    )
    (net (code "28") (name "Net-(LED25-DO)") (class "Default")
      (node (ref "LED25") (pin "2-DOUT") (pinfunction "DO_2-DOUT") (pintype "output"))
      (node (ref "LED26") (pin "4-DIN") (pinfunction "DI_4-DIN") (pintype "input"))
    )
    (net (code "29") (name "Net-(LED26-DO)") (class "Default")
      (node (ref "LED26") (pin "2-DOUT") (pinfunction "DO_2-DOUT") (pintype "output"))
      (node (ref "LED27") (pin "4-DIN") (pinfunction "DI_4-DIN") (pintype "input"))
    )
    (net (code "30") (name "Net-(LED27-DO)") (class "Default")
      (node (ref "LED27") (pin "2-DOUT") (pinfunction "DO_2-DOUT") (pintype "output"))
      (node (ref "LED28") (pin "4-DIN") (pinfunction "DI_4-DIN") (pintype "input"))
    )
    (net (code "31") (name "Net-(LED28-DO)") (class "Default")
      (node (ref "LED28") (pin "2-DOUT") (pinfunction "DO_2-DOUT") (pintype "output"))
      (node (ref "LED29") (pin "4-DIN") (pinfunction "DI_4-DIN") (pintype "input"))
    )
    (net (code "32") (name "Net-(LED29-DO)") (class "Default")
      (node (ref "LED29") (pin "2-DOUT") (pinfunction "DO_2-DOUT") (pintype "output"))
      (node (ref "LED30") (pin "4-DIN") (pinfunction "DI_4-DIN") (pintype "input"))
    )
    (net (code "33") (name "Net-(LED30-DO)") (class "Default")
      (node (ref "LED30") (pin "2-DOUT") (pinfunction "DO_2-DOUT") (pintype "output"))
      (node (ref "LED31") (pin "4-DIN") (pinfunction "DI_4-DIN") (pintype "input"))
    )
    (net (code "34") (name "Net-(LED31-DO)") (class "Default")
      (node (ref "LED31") (pin "2-DOUT") (pinfunction "DO_2-DOUT") (pintype "output"))
      (node (ref "LED32") (pin "4-DIN") (pinfunction "DI_4-DIN") (pintype "input"))
    )
    (net (code "35") (name "Net-(LED32-DO)") (class "Default")
      (node (ref "LED32") (pin "2-DOUT") (pinfunction "DO_2-DOUT") (pintype "output"))
      (node (ref "LED33") (pin "4-DIN") (pinfunction "DI_4-DIN") (pintype "input"))
    )
    (net (code "36") (name "Net-(LED33-DO)") (class "Default")
      (node (ref "LED33") (pin "2-DOUT") (pinfunction "DO_2-DOUT") (pintype "output"))
      (node (ref "LED34") (pin "4-DIN") (pinfunction "DI_4-DIN") (pintype "input"))
    )
    (net (code "37") (name "Net-(LED34-DO)") (class "Default")
      (node (ref "LED34") (pin "2-DOUT") (pinfunction "DO_2-DOUT") (pintype "output"))
      (node (ref "LED35") (pin "4-DIN") (pinfunction "DI_4-DIN") (pintype "input"))
    )
    (net (code "38") (name "Net-(LED35-DO)") (class "Default")
      (node (ref "LED35") (pin "2-DOUT") (pinfunction "DO_2-DOUT") (pintype "output"))
      (node (ref "LED36") (pin "4-DIN") (pinfunction "DI_4-DIN") (pintype "input"))
    )
    (net (code "39") (name "Net-(LED36-DO)") (class "Default")
      (node (ref "LED36") (pin "2-DOUT") (pinfunction "DO_2-DOUT") (pintype "output"))
      (node (ref "LED37") (pin "4-DIN") (pinfunction "DI_4-DIN") (pintype "input"))
    )
    (net (code "40") (name "Net-(LED37-DO)") (class "Default")
      (node (ref "LED37") (pin "2-DOUT") (pinfunction "DO_2-DOUT") (pintype "output"))
      (node (ref "LED38") (pin "4-DIN") (pinfunction "DI_4-DIN") (pintype "input"))
    )
    (net (code "41") (name "Net-(LED38-DO)") (class "Default")
      (node (ref "LED38") (pin "2-DOUT") (pinfunction "DO_2-DOUT") (pintype "output"))
      (node (ref "LED39") (pin "4-DIN") (pinfunction "DI_4-DIN") (pintype "input"))
    )
    (net (code "42") (name "Net-(LED39-DO)") (class "Default")
      (node (ref "LED39") (pin "2-DOUT") (pinfunction "DO_2-DOUT") (pintype "output"))
      (node (ref "LED40") (pin "4-DIN") (pinfunction "DI_4-DIN") (pintype "input"))
    )
    (net (code "43") (name "Net-(LED40-DO)") (class "Default")
      (node (ref "LED40") (pin "2-DOUT") (pinfunction "DO_2-DOUT") (pintype "output"))
      (node (ref "LED41") (pin "4-DIN") (pinfunction "DI_4-DIN") (pintype "input"))
    )
    (net (code "44") (name "Net-(LED41-DO)") (class "Default")
      (node (ref "LED41") (pin "2-DOUT") (pinfunction "DO_2-DOUT") (pintype "output"))
      (node (ref "LED42") (pin "4-DIN") (pinfunction "DI_4-DIN") (pintype "input"))
    )
    (net (code "45") (name "Net-(LED42-DO)") (class "Default")
      (node (ref "LED42") (pin "2-DOUT") (pinfunction "DO_2-DOUT") (pintype "output"))
      (node (ref "LED43") (pin "4-DIN") (pinfunction "DI_4-DIN") (pintype "input"))
    )
    (net (code "46") (name "Net-(LED43-DO)") (class "Default")
      (node (ref "LED43") (pin "2-DOUT") (pinfunction "DO_2-DOUT") (pintype "output"))
      (node (ref "LED44") (pin "4-DIN") (pinfunction "DI_4-DIN") (pintype "input"))
    )
    (net (code "47") (name "Net-(LED44-DO)") (class "Default")
      (node (ref "LED44") (pin "2-DOUT") (pinfunction "DO_2-DOUT") (pintype "output"))
      (node (ref "LED45") (pin "4-DIN") (pinfunction "DI_4-DIN") (pintype "input"))
    )
    (net (code "48") (name "Net-(LED45-DO)") (class "Default")
      (node (ref "LED45") (pin "2-DOUT") (pinfunction "DO_2-DOUT") (pintype "output"))
      (node (ref "LED46") (pin "4-DIN") (pinfunction "DI_4-DIN") (pintype "input"))
    )
    (net (code "49") (name "Net-(LED46-DO)") (class "Default")
      (node (ref "LED46") (pin "2-DOUT") (pinfunction "DO_2-DOUT") (pintype "output"))
      (node (ref "LED47") (pin "4-DIN") (pinfunction "DI_4-DIN") (pintype "input"))
    )
    (net (code "50") (name "Net-(LED47-DO)") (class "Default")
      (node (ref "LED47") (pin "2-DOUT") (pinfunction "DO_2-DOUT") (pintype "output"))
      (node (ref "LED48") (pin "4-DIN") (pinfunction "DI_4-DIN") (pintype "input"))
    )
    (net (code "51") (name "Net-(LED48-DO)") (class "Default")
      (node (ref "LED48") (pin "2-DOUT") (pinfunction "DO_2-DOUT") (pintype "output"))
      (node (ref "LED49") (pin "4-DIN") (pinfunction "DI_4-DIN") (pintype "input"))
    )
    (net (code "52") (name "Net-(LED49-DO)") (class "Default")
      (node (ref "LED49") (pin "2-DOUT") (pinfunction "DO_2-DOUT") (pintype "output"))
      (node (ref "LED50") (pin "4-DIN") (pinfunction "DI_4-DIN") (pintype "input"))
    )
    (net (code "53") (name "Net-(LED50-DO)") (class "Default")
      (node (ref "LED50") (pin "2-DOUT") (pinfunction "DO_2-DOUT") (pintype "output"))
      (node (ref "LED51") (pin "4-DIN") (pinfunction "DI_4-DIN") (pintype "input"))
    )
    (net (code "54") (name "Net-(LED51-DO)") (class "Default")
      (node (ref "LED51") (pin "2-DOUT") (pinfunction "DO_2-DOUT") (pintype "output"))
      (node (ref "LED52") (pin "4-DIN") (pinfunction "DI_4-DIN") (pintype "input"))
    )
    (net (code "55") (name "Net-(LED52-DO)") (class "Default")
      (node (ref "LED52") (pin "2-DOUT") (pinfunction "DO_2-DOUT") (pintype "output"))
      (node (ref "LED53") (pin "4-DIN") (pinfunction "DI_4-DIN") (pintype "input"))
    )
    (net (code "56") (name "Net-(LED53-DO)") (class "Default")
      (node (ref "LED53") (pin "2-DOUT") (pinfunction "DO_2-DOUT") (pintype "output"))
      (node (ref "LED54") (pin "4-DIN") (pinfunction "DI_4-DIN") (pintype "input"))
    )
    (net (code "57") (name "Net-(LED54-DO)") (class "Default")
      (node (ref "LED54") (pin "2-DOUT") (pinfunction "DO_2-DOUT") (pintype "output"))
      (node (ref "LED55") (pin "4-DIN") (pinfunction "DI_4-DIN") (pintype "input"))
    )
    (net (code "58") (name "Net-(LED55-DO)") (class "Default")
      (node (ref "LED55") (pin "2-DOUT") (pinfunction "DO_2-DOUT") (pintype "output"))
      (node (ref "LED56") (pin "4-DIN") (pinfunction "DI_4-DIN") (pintype "input"))
    )
    (net (code "59") (name "Net-(LED56-DO)") (class "Default")
      (node (ref "LED56") (pin "2-DOUT") (pinfunction "DO_2-DOUT") (pintype "output"))
      (node (ref "LED57") (pin "4-DIN") (pinfunction "DI_4-DIN") (pintype "input"))
    )
    (net (code "60") (name "Net-(LED57-DO)") (class "Default")
      (node (ref "LED57") (pin "2-DOUT") (pinfunction "DO_2-DOUT") (pintype "output"))
      (node (ref "LED58") (pin "4-DIN") (pinfunction "DI_4-DIN") (pintype "input"))
    )
    (net (code "61") (name "Net-(LED58-DO)") (class "Default")
      (node (ref "LED58") (pin "2-DOUT") (pinfunction "DO_2-DOUT") (pintype "output"))
      (node (ref "LED59") (pin "4-DIN") (pinfunction "DI_4-DIN") (pintype "input"))
    )
    (net (code "62") (name "Net-(LED59-DO)") (class "Default")
      (node (ref "LED59") (pin "2-DOUT") (pinfunction "DO_2-DOUT") (pintype "output"))
      (node (ref "LED60") (pin "4-DIN") (pinfunction "DI_4-DIN") (pintype "input"))
    )
    (net (code "63") (name "Net-(LED60-DO)") (class "Default")
      (node (ref "LED60") (pin "2-DOUT") (pinfunction "DO_2-DOUT") (pintype "output"))
      (node (ref "LED61") (pin "4-DIN") (pinfunction "DI_4-DIN") (pintype "input"))
    )
    (net (code "64") (name "Net-(LED61-DO)") (class "Default")
      (node (ref "LED61") (pin "2-DOUT") (pinfunction "DO_2-DOUT") (pintype "output"))
      (node (ref "LED62") (pin "4-DIN") (pinfunction "DI_4-DIN") (pintype "input"))
    )
    (net (code "65") (name "Net-(LED62-DO)") (class "Default")
      (node (ref "LED62") (pin "2-DOUT") (pinfunction "DO_2-DOUT") (pintype "output"))
      (node (ref "LED63") (pin "4-DIN") (pinfunction "DI_4-DIN") (pintype "input"))
    )
    (net (code "66") (name "Net-(LED63-DO)") (class "Default")
      (node (ref "LED63") (pin "2-DOUT") (pinfunction "DO_2-DOUT") (pintype "output"))
      (node (ref "LED64") (pin "4-DIN") (pinfunction "DI_4-DIN") (pintype "input"))
    )
    (net (code "67") (name "Net-(LED64-DO)") (class "Default")
      (node (ref "LED64") (pin "2-DOUT") (pinfunction "DO_2-DOUT") (pintype "output"))
      (node (ref "LED65") (pin "4-DIN") (pinfunction "DI_4-DIN") (pintype "input"))
    )
    (net (code "68") (name "Net-(LED65-DO)") (class "Default")
      (node (ref "LED65") (pin "2-DOUT") (pinfunction "DO_2-DOUT") (pintype "output"))
      (node (ref "LED66") (pin "4-DIN") (pinfunction "DI_4-DIN") (pintype "input"))
    )
    (net (code "69") (name "Net-(LED66-DO)") (class "Default")
      (node (ref "LED66") (pin "2-DOUT") (pinfunction "DO_2-DOUT") (pintype "output"))
      (node (ref "LED67") (pin "4-DIN") (pinfunction "DI_4-DIN") (pintype "input"))
    )
    (net (code "70") (name "Net-(LED67-DO)") (class "Default")
      (node (ref "LED67") (pin "2-DOUT") (pinfunction "DO_2-DOUT") (pintype "output"))
      (node (ref "LED68") (pin "4-DIN") (pinfunction "DI_4-DIN") (pintype "input"))
    )
    (net (code "71") (name "Net-(LED68-DO)") (class "Default")
      (node (ref "LED68") (pin "2-DOUT") (pinfunction "DO_2-DOUT") (pintype "output"))
      (node (ref "LED69") (pin "4-DIN") (pinfunction "DI_4-DIN") (pintype "input"))
    )
    (net (code "72") (name "Net-(LED69-DO)") (class "Default")
      (node (ref "LED69") (pin "2-DOUT") (pinfunction "DO_2-DOUT") (pintype "output"))
      (node (ref "LED70") (pin "4-DIN") (pinfunction "DI_4-DIN") (pintype "input"))
    )
    (net (code "73") (name "Net-(LED70-DO)") (class "Default")
      (node (ref "LED70") (pin "2-DOUT") (pinfunction "DO_2-DOUT") (pintype "output"))
      (node (ref "LED71") (pin "4-DIN") (pinfunction "DI_4-DIN") (pintype "input"))
    )
    (net (code "74") (name "Net-(LED71-DO)") (class "Default")
      (node (ref "LED71") (pin "2-DOUT") (pinfunction "DO_2-DOUT") (pintype "output"))
      (node (ref "LED72") (pin "4-DIN") (pinfunction "DI_4-DIN") (pintype "input"))
    )
    (net (code "75") (name "Net-(LED72-DO)") (class "Default")
      (node (ref "LED72") (pin "2-DOUT") (pinfunction "DO_2-DOUT") (pintype "output"))
      (node (ref "LED73") (pin "4-DIN") (pinfunction "DI_4-DIN") (pintype "input"))
    )
    (net (code "76") (name "Net-(LED73-DO)") (class "Default")
      (node (ref "LED73") (pin "2-DOUT") (pinfunction "DO_2-DOUT") (pintype "output"))
      (node (ref "LED74") (pin "4-DIN") (pinfunction "DI_4-DIN") (pintype "input"))
    )
    (net (code "77") (name "Net-(LED74-DO)") (class "Default")
      (node (ref "LED74") (pin "2-DOUT") (pinfunction "DO_2-DOUT") (pintype "output"))
      (node (ref "LED75") (pin "4-DIN") (pinfunction "DI_4-DIN") (pintype "input"))
    )
    (net (code "78") (name "Net-(LED75-DO)") (class "Default")
      (node (ref "LED75") (pin "2-DOUT") (pinfunction "DO_2-DOUT") (pintype "output"))
      (node (ref "LED76") (pin "4-DIN") (pinfunction "DI_4-DIN") (pintype "input"))
    )
    (net (code "79") (name "Net-(LED76-DO)") (class "Default")
      (node (ref "LED76") (pin "2-DOUT") (pinfunction "DO_2-DOUT") (pintype "output"))
      (node (ref "LED77") (pin "4-DIN") (pinfunction "DI_4-DIN") (pintype "input"))
    )
    (net (code "80") (name "Net-(LED77-DO)") (class "Default")
      (node (ref "LED77") (pin "2-DOUT") (pinfunction "DO_2-DOUT") (pintype "output"))
      (node (ref "LED78") (pin "4-DIN") (pinfunction "DI_4-DIN") (pintype "input"))
    )
    (net (code "81") (name "Net-(LED78-DO)") (class "Default")
      (node (ref "LED78") (pin "2-DOUT") (pinfunction "DO_2-DOUT") (pintype "output"))
      (node (ref "LED79") (pin "4-DIN") (pinfunction "DI_4-DIN") (pintype "input"))
    )
    (net (code "82") (name "Net-(LED79-DO)") (class "Default")
      (node (ref "LED79") (pin "2-DOUT") (pinfunction "DO_2-DOUT") (pintype "output"))
      (node (ref "LED80") (pin "4-DIN") (pinfunction "DI_4-DIN") (pintype "input"))
    )
    (net (code "83") (name "Net-(LED80-DO)") (class "Default")
      (node (ref "LED80") (pin "2-DOUT") (pinfunction "DO_2-DOUT") (pintype "output"))
      (node (ref "LED81") (pin "4-DIN") (pinfunction "DI_4-DIN") (pintype "input"))
    )
    (net (code "84") (name "Net-(LED81-DO)") (class "Default")
      (node (ref "LED81") (pin "2-DOUT") (pinfunction "DO_2-DOUT") (pintype "output"))
      (node (ref "LED82") (pin "4-DIN") (pinfunction "DI_4-DIN") (pintype "input"))
    )
    (net (code "85") (name "Net-(LED82-DO)") (class "Default")
      (node (ref "LED82") (pin "2-DOUT") (pinfunction "DO_2-DOUT") (pintype "output"))
      (node (ref "LED83") (pin "4-DIN") (pinfunction "DI_4-DIN") (pintype "input"))
    )
    (net (code "86") (name "Net-(LED83-DO)") (class "Default")
      (node (ref "LED83") (pin "2-DOUT") (pinfunction "DO_2-DOUT") (pintype "output"))
      (node (ref "LED84") (pin "4-DIN") (pinfunction "DI_4-DIN") (pintype "input"))
    )
    (net (code "87") (name "Net-(LED84-DO)") (class "Default")
      (node (ref "LED84") (pin "2-DOUT") (pinfunction "DO_2-DOUT") (pintype "output"))
      (node (ref "LED85") (pin "4-DIN") (pinfunction "DI_4-DIN") (pintype "input"))
    )
    (net (code "88") (name "Net-(LED85-DO)") (class "Default")
      (node (ref "LED85") (pin "2-DOUT") (pinfunction "DO_2-DOUT") (pintype "output"))
      (node (ref "LED86") (pin "4-DIN") (pinfunction "DI_4-DIN") (pintype "input"))
    )
    (net (code "89") (name "Net-(LED86-DO)") (class "Default")
      (node (ref "LED86") (pin "2-DOUT") (pinfunction "DO_2-DOUT") (pintype "output"))
      (node (ref "LED87") (pin "4-DIN") (pinfunction "DI_4-DIN") (pintype "input"))
    )
    (net (code "90") (name "Net-(LED87-DO)") (class "Default")
      (node (ref "LED87") (pin "2-DOUT") (pinfunction "DO_2-DOUT") (pintype "output"))
      (node (ref "LED88") (pin "4-DIN") (pinfunction "DI_4-DIN") (pintype "input"))
    )
    (net (code "91") (name "Net-(LED88-DO)") (class "Default")
      (node (ref "LED88") (pin "2-DOUT") (pinfunction "DO_2-DOUT") (pintype "output"))
      (node (ref "LED89") (pin "4-DIN") (pinfunction "DI_4-DIN") (pintype "input"))
    )
    (net (code "92") (name "Net-(LED89-DO)") (class "Default")
      (node (ref "LED89") (pin "2-DOUT") (pinfunction "DO_2-DOUT") (pintype "output"))
      (node (ref "LED90") (pin "4-DIN") (pinfunction "DI_4-DIN") (pintype "input"))
    )
    (net (code "93") (name "Net-(LED90-DO)") (class "Default")
      (node (ref "LED90") (pin "2-DOUT") (pinfunction "DO_2-DOUT") (pintype "output"))
      (node (ref "LED91") (pin "4-DIN") (pinfunction "DI_4-DIN") (pintype "input"))
    )
    (net (code "94") (name "Net-(LED91-DO)") (class "Default")
      (node (ref "LED91") (pin "2-DOUT") (pinfunction "DO_2-DOUT") (pintype "output"))
      (node (ref "LED92") (pin "4-DIN") (pinfunction "DI_4-DIN") (pintype "input"))
    )
    (net (code "95") (name "Net-(LED92-DO)") (class "Default")
      (node (ref "LED92") (pin "2-DOUT") (pinfunction "DO_2-DOUT") (pintype "output"))
      (node (ref "LED93") (pin "4-DIN") (pinfunction "DI_4-DIN") (pintype "input"))
    )
    (net (code "96") (name "Net-(LED93-DO)") (class "Default")
      (node (ref "LED93") (pin "2-DOUT") (pinfunction "DO_2-DOUT") (pintype "output"))
      (node (ref "LED94") (pin "4-DIN") (pinfunction "DI_4-DIN") (pintype "input"))
    )
    (net (code "97") (name "Net-(LED94-DO)") (class "Default")
      (node (ref "LED94") (pin "2-DOUT") (pinfunction "DO_2-DOUT") (pintype "output"))
      (node (ref "LED95") (pin "4-DIN") (pinfunction "DI_4-DIN") (pintype "input"))
    )
    (net (code "98") (name "Net-(LED95-DO)") (class "Default")
      (node (ref "LED95") (pin "2-DOUT") (pinfunction "DO_2-DOUT") (pintype "output"))
      (node (ref "LED96") (pin "4-DIN") (pinfunction "DI_4-DIN") (pintype "input"))
    )
    (net (code "99") (name "Net-(LED96-DO)") (class "Default")
      (node (ref "LED96") (pin "2-DOUT") (pinfunction "DO_2-DOUT") (pintype "output"))
      (node (ref "LED97") (pin "4-DIN") (pinfunction "DI_4-DIN") (pintype "input"))
    )
    (net (code "100") (name "Net-(LED97-DO)") (class "Default")
      (node (ref "LED97") (pin "2-DOUT") (pinfunction "DO_2-DOUT") (pintype "output"))
      (node (ref "LED98") (pin "4-DIN") (pinfunction "DI_4-DIN") (pintype "input"))
    )
    (net (code "101") (name "Net-(LED98-DO)") (class "Default")
      (node (ref "LED98") (pin "2-DOUT") (pinfunction "DO_2-DOUT") (pintype "output"))
      (node (ref "LED99") (pin "4-DIN") (pinfunction "DI_4-DIN") (pintype "input"))
    )
    (net (code "102") (name "Net-(LED100-DI)") (class "Default")
      (node (ref "LED100") (pin "4-DIN") (pinfunction "DI_4-DIN") (pintype "input"))
      (node (ref "LED99") (pin "2-DOUT") (pinfunction "DO_2-DOUT") (pintype "output"))
    )
    (net (code "103") (name "Net-(LED100-DO)") (class "Default")
      (node (ref "LED100") (pin "2-DOUT") (pinfunction "DO_2-DOUT") (pintype "output"))
      (node (ref "LED101") (pin "4-DIN") (pinfunction "DI_4-DIN") (pintype "input"))
    )
    (net (code "104") (name "Net-(LED101-DO)") (class "Default")
      (node (ref "LED101") (pin "2-DOUT") (pinfunction "DO_2-DOUT") (pintype "output"))
      (node (ref "LED102") (pin "4-DIN") (pinfunction "DI_4-DIN") (pintype "input"))
    )
    (net (code "105") (name "Net-(LED102-DO)") (class "Default")
      (node (ref "LED102") (pin "2-DOUT") (pinfunction "DO_2-DOUT") (pintype "output"))
      (node (ref "LED103") (pin "4-DIN") (pinfunction "DI_4-DIN") (pintype "input"))
    )
    (net (code "106") (name "Net-(LED103-DO)") (class "Default")
      (node (ref "LED103") (pin "2-DOUT") (pinfunction "DO_2-DOUT") (pintype "output"))
      (node (ref "LED104") (pin "4-DIN") (pinfunction "DI_4-DIN") (pintype "input"))
    )
    (net (code "107") (name "Net-(LED104-DO)") (class "Default")
      (node (ref "LED104") (pin "2-DOUT") (pinfunction "DO_2-DOUT") (pintype "output"))
      (node (ref "LED105") (pin "4-DIN") (pinfunction "DI_4-DIN") (pintype "input"))
    )
    (net (code "108") (name "Net-(LED105-DO)") (class "Default")
      (node (ref "LED105") (pin "2-DOUT") (pinfunction "DO_2-DOUT") (pintype "output"))
      (node (ref "LED106") (pin "4-DIN") (pinfunction "DI_4-DIN") (pintype "input"))
    )
    (net (code "109") (name "Net-(LED106-DO)") (class "Default")
      (node (ref "LED106") (pin "2-DOUT") (pinfunction "DO_2-DOUT") (pintype "output"))
      (node (ref "LED107") (pin "4-DIN") (pinfunction "DI_4-DIN") (pintype "input"))
    )
    (net (code "110") (name "Net-(LED107-DO)") (class "Default")
      (node (ref "LED107") (pin "2-DOUT") (pinfunction "DO_2-DOUT") (pintype "output"))
      (node (ref "LED108") (pin "4-DIN") (pinfunction "DI_4-DIN") (pintype "input"))
    )
    (net (code "111") (name "Net-(LED108-DO)") (class "Default")
      (node (ref "LED108") (pin "2-DOUT") (pinfunction "DO_2-DOUT") (pintype "output"))
      (node (ref "LED109") (pin "4-DIN") (pinfunction "DI_4-DIN") (pintype "input"))
    )
    (net (code "112") (name "Net-(LED109-DO)") (class "Default")
      (node (ref "LED109") (pin "2-DOUT") (pinfunction "DO_2-DOUT") (pintype "output"))
      (node (ref "LED110") (pin "4-DIN") (pinfunction "DI_4-DIN") (pintype "input"))
    )
    (net (code "113") (name "Net-(LED110-DO)") (class "Default")
      (node (ref "LED110") (pin "2-DOUT") (pinfunction "DO_2-DOUT") (pintype "output"))
      (node (ref "LED111") (pin "4-DIN") (pinfunction "DI_4-DIN") (pintype "input"))
    )
    (net (code "114") (name "Net-(LED111-DO)") (class "Default")
      (node (ref "LED111") (pin "2-DOUT") (pinfunction "DO_2-DOUT") (pintype "output"))
      (node (ref "LED112") (pin "4-DIN") (pinfunction "DI_4-DIN") (pintype "input"))
    )
    (net (code "115") (name "Net-(LED112-DO)") (class "Default")
      (node (ref "LED112") (pin "2-DOUT") (pinfunction "DO_2-DOUT") (pintype "output"))
      (node (ref "LED113") (pin "4-DIN") (pinfunction "DI_4-DIN") (pintype "input"))
    )
    (net (code "116") (name "Net-(LED113-DO)") (class "Default")
      (node (ref "LED113") (pin "2-DOUT") (pinfunction "DO_2-DOUT") (pintype "output"))
      (node (ref "LED114") (pin "4-DIN") (pinfunction "DI_4-DIN") (pintype "input"))
    )
    (net (code "117") (name "Net-(LED114-DO)") (class "Default")
      (node (ref "LED114") (pin "2-DOUT") (pinfunction "DO_2-DOUT") (pintype "output"))
      (node (ref "LED115") (pin "4-DIN") (pinfunction "DI_4-DIN") (pintype "input"))
    )
    (net (code "118") (name "Net-(LED115-DO)") (class "Default")
      (node (ref "LED115") (pin "2-DOUT") (pinfunction "DO_2-DOUT") (pintype "output"))
      (node (ref "LED116") (pin "4-DIN") (pinfunction "DI_4-DIN") (pintype "input"))
    )
    (net (code "119") (name "Net-(LED116-DO)") (class "Default")
      (node (ref "LED116") (pin "2-DOUT") (pinfunction "DO_2-DOUT") (pintype "output"))
      (node (ref "LED117") (pin "4-DIN") (pinfunction "DI_4-DIN") (pintype "input"))
    )
    (net (code "120") (name "Net-(LED117-DO)") (class "Default")
      (node (ref "LED117") (pin "2-DOUT") (pinfunction "DO_2-DOUT") (pintype "output"))
      (node (ref "LED118") (pin "4-DIN") (pinfunction "DI_4-DIN") (pintype "input"))
    )
    (net (code "121") (name "Net-(LED118-DO)") (class "Default")
      (node (ref "LED118") (pin "2-DOUT") (pinfunction "DO_2-DOUT") (pintype "output"))
      (node (ref "LED119") (pin "4-DIN") (pinfunction "DI_4-DIN") (pintype "input"))
    )
    (net (code "122") (name "Net-(LED119-DO)") (class "Default")
      (node (ref "LED119") (pin "2-DOUT") (pinfunction "DO_2-DOUT") (pintype "output"))
      (node (ref "LED120") (pin "4-DIN") (pinfunction "DI_4-DIN") (pintype "input"))
    )
    (net (code "123") (name "Net-(LED120-DO)") (class "Default")
      (node (ref "LED120") (pin "2-DOUT") (pinfunction "DO_2-DOUT") (pintype "output"))
      (node (ref "LED121") (pin "4-DIN") (pinfunction "DI_4-DIN") (pintype "input"))
    )
    (net (code "124") (name "Net-(LED121-DO)") (class "Default")
      (node (ref "LED121") (pin "2-DOUT") (pinfunction "DO_2-DOUT") (pintype "output"))
      (node (ref "LED122") (pin "4-DIN") (pinfunction "DI_4-DIN") (pintype "input"))
    )
    (net (code "125") (name "Net-(LED122-DO)") (class "Default")
      (node (ref "LED122") (pin "2-DOUT") (pinfunction "DO_2-DOUT") (pintype "output"))
      (node (ref "LED123") (pin "4-DIN") (pinfunction "DI_4-DIN") (pintype "input"))
    )
    (net (code "126") (name "Net-(LED123-DO)") (class "Default")
      (node (ref "LED123") (pin "2-DOUT") (pinfunction "DO_2-DOUT") (pintype "output"))
      (node (ref "LED124") (pin "4-DIN") (pinfunction "DI_4-DIN") (pintype "input"))
    )
    (net (code "127") (name "Net-(LED124-DO)") (class "Default")
      (node (ref "LED124") (pin "2-DOUT") (pinfunction "DO_2-DOUT") (pintype "output"))
      (node (ref "LED125") (pin "4-DIN") (pinfunction "DI_4-DIN") (pintype "input"))
    )
    (net (code "128") (name "Net-(LED125-DO)") (class "Default")
      (node (ref "LED125") (pin "2-DOUT") (pinfunction "DO_2-DOUT") (pintype "output"))
      (node (ref "LED126") (pin "4-DIN") (pinfunction "DI_4-DIN") (pintype "input"))
    )
    (net (code "129") (name "Net-(LED126-DO)") (class "Default")
      (node (ref "LED126") (pin "2-DOUT") (pinfunction "DO_2-DOUT") (pintype "output"))
      (node (ref "LED127") (pin "4-DIN") (pinfunction "DI_4-DIN") (pintype "input"))
    )
    (net (code "130") (name "Net-(LED127-DO)") (class "Default")
      (node (ref "LED127") (pin "2-DOUT") (pinfunction "DO_2-DOUT") (pintype "output"))
      (node (ref "LED128") (pin "4-DIN") (pinfunction "DI_4-DIN") (pintype "input"))
    )
    (net (code "131") (name "Net-(LED128-DO)") (class "Default")
      (node (ref "LED128") (pin "2-DOUT") (pinfunction "DO_2-DOUT") (pintype "output"))
      (node (ref "LED129") (pin "4-DIN") (pinfunction "DI_4-DIN") (pintype "input"))
    )
    (net (code "132") (name "Net-(LED129-DO)") (class "Default")
      (node (ref "LED129") (pin "2-DOUT") (pinfunction "DO_2-DOUT") (pintype "output"))
      (node (ref "LED130") (pin "4-DIN") (pinfunction "DI_4-DIN") (pintype "input"))
    )
    (net (code "133") (name "Net-(LED130-DO)") (class "Default")
      (node (ref "LED130") (pin "2-DOUT") (pinfunction "DO_2-DOUT") (pintype "output"))
      (node (ref "LED131") (pin "4-DIN") (pinfunction "DI_4-DIN") (pintype "input"))
    )
    (net (code "134") (name "Net-(LED131-DO)") (class "Default")
      (node (ref "LED131") (pin "2-DOUT") (pinfunction "DO_2-DOUT") (pintype "output"))
      (node (ref "LED132") (pin "4-DIN") (pinfunction "DI_4-DIN") (pintype "input"))
    )
    (net (code "135") (name "Net-(LED132-DO)") (class "Default")
      (node (ref "LED132") (pin "2-DOUT") (pinfunction "DO_2-DOUT") (pintype "output"))
      (node (ref "LED133") (pin "4-DIN") (pinfunction "DI_4-DIN") (pintype "input"))
    )
    (net (code "136") (name "Net-(LED133-DO)") (class "Default")
      (node (ref "LED133") (pin "2-DOUT") (pinfunction "DO_2-DOUT") (pintype "output"))
      (node (ref "LED134") (pin "4-DIN") (pinfunction "DI_4-DIN") (pintype "input"))
    )
    (net (code "137") (name "Net-(LED134-DO)") (class "Default")
      (node (ref "LED134") (pin "2-DOUT") (pinfunction "DO_2-DOUT") (pintype "output"))
      (node (ref "LED135") (pin "4-DIN") (pinfunction "DI_4-DIN") (pintype "input"))
    )
    (net (code "138") (name "Net-(LED135-DO)") (class "Default")
      (node (ref "LED135") (pin "2-DOUT") (pinfunction "DO_2-DOUT") (pintype "output"))
      (node (ref "LED136") (pin "4-DIN") (pinfunction "DI_4-DIN") (pintype "input"))
    )
    (net (code "139") (name "Net-(LED136-DO)") (class "Default")
      (node (ref "LED136") (pin "2-DOUT") (pinfunction "DO_2-DOUT") (pintype "output"))
      (node (ref "LED137") (pin "4-DIN") (pinfunction "DI_4-DIN") (pintype "input"))
    )
    (net (code "140") (name "Net-(LED137-DO)") (class "Default")
      (node (ref "LED137") (pin "2-DOUT") (pinfunction "DO_2-DOUT") (pintype "output"))
      (node (ref "LED138") (pin "4-DIN") (pinfunction "DI_4-DIN") (pintype "input"))
    )
    (net (code "141") (name "Net-(LED138-DO)") (class "Default")
      (node (ref "LED138") (pin "2-DOUT") (pinfunction "DO_2-DOUT") (pintype "output"))
      (node (ref "LED139") (pin "4-DIN") (pinfunction "DI_4-DIN") (pintype "input"))
    )
    (net (code "142") (name "Net-(LED139-DO)") (class "Default")
      (node (ref "LED139") (pin "2-DOUT") (pinfunction "DO_2-DOUT") (pintype "output"))
      (node (ref "LED140") (pin "4-DIN") (pinfunction "DI_4-DIN") (pintype "input"))
    )
    (net (code "143") (name "Net-(LED140-DO)") (class "Default")
      (node (ref "LED140") (pin "2-DOUT") (pinfunction "DO_2-DOUT") (pintype "output"))
      (node (ref "LED141") (pin "4-DIN") (pinfunction "DI_4-DIN") (pintype "input"))
    )
    (net (code "144") (name "Net-(LED141-DO)") (class "Default")
      (node (ref "LED141") (pin "2-DOUT") (pinfunction "DO_2-DOUT") (pintype "output"))
      (node (ref "LED142") (pin "4-DIN") (pinfunction "DI_4-DIN") (pintype "input"))
    )
    (net (code "145") (name "Net-(LED142-DO)") (class "Default")
      (node (ref "LED142") (pin "2-DOUT") (pinfunction "DO_2-DOUT") (pintype "output"))
      (node (ref "LED143") (pin "4-DIN") (pinfunction "DI_4-DIN") (pintype "input"))
    )
    (net (code "146") (name "Net-(LED143-DO)") (class "Default")
      (node (ref "LED143") (pin "2-DOUT") (pinfunction "DO_2-DOUT") (pintype "output"))
      (node (ref "LED144") (pin "4-DIN") (pinfunction "DI_4-DIN") (pintype "input"))
    )
    (net (code "147") (name "Net-(LED144-DO)") (class "Default")
      (node (ref "LED144") (pin "2-DOUT") (pinfunction "DO_2-DOUT") (pintype "output"))
      (node (ref "LED145") (pin "4-DIN") (pinfunction "DI_4-DIN") (pintype "input"))
    )
    (net (code "148") (name "Net-(LED145-DO)") (class "Default")
      (node (ref "LED145") (pin "2-DOUT") (pinfunction "DO_2-DOUT") (pintype "output"))
      (node (ref "LED146") (pin "4-DIN") (pinfunction "DI_4-DIN") (pintype "input"))
    )
    (net (code "149") (name "Net-(LED146-DO)") (class "Default")
      (node (ref "LED146") (pin "2-DOUT") (pinfunction "DO_2-DOUT") (pintype "output"))
      (node (ref "LED147") (pin "4-DIN") (pinfunction "DI_4-DIN") (pintype "input"))
    )
    (net (code "150") (name "Net-(LED147-DO)") (class "Default")
      (node (ref "LED147") (pin "2-DOUT") (pinfunction "DO_2-DOUT") (pintype "output"))
      (node (ref "LED148") (pin "4-DIN") (pinfunction "DI_4-DIN") (pintype "input"))
    )
    (net (code "151") (name "Net-(LED148-DO)") (class "Default")
      (node (ref "LED148") (pin "2-DOUT") (pinfunction "DO_2-DOUT") (pintype "output"))
      (node (ref "LED149") (pin "4-DIN") (pinfunction "DI_4-DIN") (pintype "input"))
    )
    (net (code "152") (name "Net-(LED149-DO)") (class "Default")
      (node (ref "LED149") (pin "2-DOUT") (pinfunction "DO_2-DOUT") (pintype "output"))
      (node (ref "LED150") (pin "4-DIN") (pinfunction "DI_4-DIN") (pintype "input"))
    )
    (net (code "153") (name "Net-(LED150-DO)") (class "Default")
      (node (ref "LED150") (pin "2-DOUT") (pinfunction "DO_2-DOUT") (pintype "output"))
      (node (ref "LED151") (pin "4-DIN") (pinfunction "DI_4-DIN") (pintype "input"))
    )
    (net (code "154") (name "Net-(LED151-DO)") (class "Default")
      (node (ref "LED151") (pin "2-DOUT") (pinfunction "DO_2-DOUT") (pintype "output"))
      (node (ref "LED152") (pin "4-DIN") (pinfunction "DI_4-DIN") (pintype "input"))
    )
    (net (code "155") (name "Net-(LED152-DO)") (class "Default")
      (node (ref "LED152") (pin "2-DOUT") (pinfunction "DO_2-DOUT") (pintype "output"))
      (node (ref "LED153") (pin "4-DIN") (pinfunction "DI_4-DIN") (pintype "input"))
    )
    (net (code "156") (name "Net-(LED153-DO)") (class "Default")
      (node (ref "LED153") (pin "2-DOUT") (pinfunction "DO_2-DOUT") (pintype "output"))
      (node (ref "LED154") (pin "4-DIN") (pinfunction "DI_4-DIN") (pintype "input"))
    )
    (net (code "157") (name "Net-(LED154-DO)") (class "Default")
      (node (ref "LED154") (pin "2-DOUT") (pinfunction "DO_2-DOUT") (pintype "output"))
      (node (ref "LED155") (pin "4-DIN") (pinfunction "DI_4-DIN") (pintype "input"))
    )
    (net (code "158") (name "Net-(LED155-DO)") (class "Default")
      (node (ref "LED155") (pin "2-DOUT") (pinfunction "DO_2-DOUT") (pintype "output"))
      (node (ref "LED156") (pin "4-DIN") (pinfunction "DI_4-DIN") (pintype "input"))
    )
    (net (code "159") (name "Net-(LED156-DO)") (class "Default")
      (node (ref "LED156") (pin "2-DOUT") (pinfunction "DO_2-DOUT") (pintype "output"))
      (node (ref "LED157") (pin "4-DIN") (pinfunction "DI_4-DIN") (pintype "input"))
    )
    (net (code "160") (name "Net-(LED157-DO)") (class "Default")
      (node (ref "LED157") (pin "2-DOUT") (pinfunction "DO_2-DOUT") (pintype "output"))
      (node (ref "LED158") (pin "4-DIN") (pinfunction "DI_4-DIN") (pintype "input"))
    )
    (net (code "161") (name "Net-(LED158-DO)") (class "Default")
      (node (ref "LED158") (pin "2-DOUT") (pinfunction "DO_2-DOUT") (pintype "output"))
      (node (ref "LED159") (pin "4-DIN") (pinfunction "DI_4-DIN") (pintype "input"))
    )
    (net (code "162") (name "Net-(LED159-DO)") (class "Default")
      (node (ref "LED159") (pin "2-DOUT") (pinfunction "DO_2-DOUT") (pintype "output"))
      (node (ref "LED160") (pin "4-DIN") (pinfunction "DI_4-DIN") (pintype "input"))
    )
    (net (code "163") (name "Net-(LED160-DO)") (class "Default")
      (node (ref "LED160") (pin "2-DOUT") (pinfunction "DO_2-DOUT") (pintype "output"))
      (node (ref "LED161") (pin "4-DIN") (pinfunction "DI_4-DIN") (pintype "input"))
    )
    (net (code "164") (name "VCC") (class "Default")
      (node (ref "JP1") (pin "1") (pinfunction "1_1") (pintype "passive"))
      (node (ref "JP2") (pin "1") (pinfunction "1_1") (pintype "passive"))
      (node (ref "JP3") (pin "1") (pinfunction "1_1") (pintype "passive"))
      (node (ref "JP4") (pin "1") (pinfunction "1_1") (pintype "passive"))
      (node (ref "JP5") (pin "1") (pinfunction "1_1") (pintype "passive"))
      (node (ref "LED1") (pin "1-VDD") (pinfunction "VDD_1-VDD") (pintype "power_in"))
      (node (ref "LED10") (pin "1-VDD") (pinfunction "VDD_1-VDD") (pintype "power_in"))
      (node (ref "LED100") (pin "1-VDD") (pinfunction "VDD_1-VDD") (pintype "power_in"))
      (node (ref "LED101") (pin "1-VDD") (pinfunction "VDD_1-VDD") (pintype "power_in"))
      (node (ref "LED102") (pin "1-VDD") (pinfunction "VDD_1-VDD") (pintype "power_in"))
      (node (ref "LED103") (pin "1-VDD") (pinfunction "VDD_1-VDD") (pintype "power_in"))
      (node (ref "LED104") (pin "1-VDD") (pinfunction "VDD_1-VDD") (pintype "power_in"))
      (node (ref "LED105") (pin "1-VDD") (pinfunction "VDD_1-VDD") (pintype "power_in"))
      (node (ref "LED106") (pin "1-VDD") (pinfunction "VDD_1-VDD") (pintype "power_in"))
      (node (ref "LED107") (pin "1-VDD") (pinfunction "VDD_1-VDD") (pintype "power_in"))
      (node (ref "LED108") (pin "1-VDD") (pinfunction "VDD_1-VDD") (pintype "power_in"))
      (node (ref "LED109") (pin "1-VDD") (pinfunction "VDD_1-VDD") (pintype "power_in"))
      (node (ref "LED11") (pin "1-VDD") (pinfunction "VDD_1-VDD") (pintype "power_in"))
      (node (ref "LED110") (pin "1-VDD") (pinfunction "VDD_1-VDD") (pintype "power_in"))
      (node (ref "LED111") (pin "1-VDD") (pinfunction "VDD_1-VDD") (pintype "power_in"))
      (node (ref "LED112") (pin "1-VDD") (pinfunction "VDD_1-VDD") (pintype "power_in"))
      (node (ref "LED113") (pin "1-VDD") (pinfunction "VDD_1-VDD") (pintype "power_in"))
      (node (ref "LED114") (pin "1-VDD") (pinfunction "VDD_1-VDD") (pintype "power_in"))
      (node (ref "LED115") (pin "1-VDD") (pinfunction "VDD_1-VDD") (pintype "power_in"))
      (node (ref "LED116") (pin "1-VDD") (pinfunction "VDD_1-VDD") (pintype "power_in"))
      (node (ref "LED117") (pin "1-VDD") (pinfunction "VDD_1-VDD") (pintype "power_in"))
      (node (ref "LED118") (pin "1-VDD") (pinfunction "VDD_1-VDD") (pintype "power_in"))
      (node (ref "LED119") (pin "1-VDD") (pinfunction "VDD_1-VDD") (pintype "power_in"))
      (node (ref "LED12") (pin "1-VDD") (pinfunction "VDD_1-VDD") (pintype "power_in"))
      (node (ref "LED120") (pin "1-VDD") (pinfunction "VDD_1-VDD") (pintype "power_in"))
      (node (ref "LED121") (pin "1-VDD") (pinfunction "VDD_1-VDD") (pintype "power_in"))
      (node (ref "LED122") (pin "1-VDD") (pinfunction "VDD_1-VDD") (pintype "power_in"))
      (node (ref "LED123") (pin "1-VDD") (pinfunction "VDD_1-VDD") (pintype "power_in"))
      (node (ref "LED124") (pin "1-VDD") (pinfunction "VDD_1-VDD") (pintype "power_in"))
      (node (ref "LED125") (pin "1-VDD") (pinfunction "VDD_1-VDD") (pintype "power_in"))
      (node (ref "LED126") (pin "1-VDD") (pinfunction "VDD_1-VDD") (pintype "power_in"))
      (node (ref "LED127") (pin "1-VDD") (pinfunction "VDD_1-VDD") (pintype "power_in"))
      (node (ref "LED128") (pin "1-VDD") (pinfunction "VDD_1-VDD") (pintype "power_in"))
      (node (ref "LED129") (pin "1-VDD") (pinfunction "VDD_1-VDD") (pintype "power_in"))
      (node (ref "LED13") (pin "1-VDD") (pinfunction "VDD_1-VDD") (pintype "power_in"))
      (node (ref "LED130") (pin "1-VDD") (pinfunction "VDD_1-VDD") (pintype "power_in"))
      (node (ref "LED131") (pin "1-VDD") (pinfunction "VDD_1-VDD") (pintype "power_in"))
      (node (ref "LED132") (pin "1-VDD") (pinfunction "VDD_1-VDD") (pintype "power_in"))
      (node (ref "LED133") (pin "1-VDD") (pinfunction "VDD_1-VDD") (pintype "power_in"))
      (node (ref "LED134") (pin "1-VDD") (pinfunction "VDD_1-VDD") (pintype "power_in"))
      (node (ref "LED135") (pin "1-VDD") (pinfunction "VDD_1-VDD") (pintype "power_in"))
      (node (ref "LED136") (pin "1-VDD") (pinfunction "VDD_1-VDD") (pintype "power_in"))
      (node (ref "LED137") (pin "1-VDD") (pinfunction "VDD_1-VDD") (pintype "power_in"))
      (node (ref "LED138") (pin "1-VDD") (pinfunction "VDD_1-VDD") (pintype "power_in"))
      (node (ref "LED139") (pin "1-VDD") (pinfunction "VDD_1-VDD") (pintype "power_in"))
      (node (ref "LED14") (pin "1-VDD") (pinfunction "VDD_1-VDD") (pintype "power_in"))
      (node (ref "LED140") (pin "1-VDD") (pinfunction "VDD_1-VDD") (pintype "power_in"))
      (node (ref "LED141") (pin "1-VDD") (pinfunction "VDD_1-VDD") (pintype "power_in"))
      (node (ref "LED142") (pin "1-VDD") (pinfunction "VDD_1-VDD") (pintype "power_in"))
      (node (ref "LED143") (pin "1-VDD") (pinfunction "VDD_1-VDD") (pintype "power_in"))
      (node (ref "LED144") (pin "1-VDD") (pinfunction "VDD_1-VDD") (pintype "power_in"))
      (node (ref "LED145") (pin "1-VDD") (pinfunction "VDD_1-VDD") (pintype "power_in"))
      (node (ref "LED146") (pin "1-VDD") (pinfunction "VDD_1-VDD") (pintype "power_in"))
      (node (ref "LED147") (pin "1-VDD") (pinfunction "VDD_1-VDD") (pintype "power_in"))
      (node (ref "LED148") (pin "1-VDD") (pinfunction "VDD_1-VDD") (pintype "power_in"))
      (node (ref "LED149") (pin "1-VDD") (pinfunction "VDD_1-VDD") (pintype "power_in"))
      (node (ref "LED15") (pin "1-VDD") (pinfunction "VDD_1-VDD") (pintype "power_in"))
      (node (ref "LED150") (pin "1-VDD") (pinfunction "VDD_1-VDD") (pintype "power_in"))
      (node (ref "LED151") (pin "1-VDD") (pinfunction "VDD_1-VDD") (pintype "power_in"))
      (node (ref "LED152") (pin "1-VDD") (pinfunction "VDD_1-VDD") (pintype "power_in"))
      (node (ref "LED153") (pin "1-VDD") (pinfunction "VDD_1-VDD") (pintype "power_in"))
      (node (ref "LED154") (pin "1-VDD") (pinfunction "VDD_1-VDD") (pintype "power_in"))
      (node (ref "LED155") (pin "1-VDD") (pinfunction "VDD_1-VDD") (pintype "power_in"))
      (node (ref "LED156") (pin "1-VDD") (pinfunction "VDD_1-VDD") (pintype "power_in"))
      (node (ref "LED157") (pin "1-VDD") (pinfunction "VDD_1-VDD") (pintype "power_in"))
      (node (ref "LED158") (pin "1-VDD") (pinfunction "VDD_1-VDD") (pintype "power_in"))
      (node (ref "LED159") (pin "1-VDD") (pinfunction "VDD_1-VDD") (pintype "power_in"))
      (node (ref "LED16") (pin "1-VDD") (pinfunction "VDD_1-VDD") (pintype "power_in"))
      (node (ref "LED160") (pin "1-VDD") (pinfunction "VDD_1-VDD") (pintype "power_in"))
      (node (ref "LED161") (pin "1-VDD") (pinfunction "VDD_1-VDD") (pintype "power_in"))
      (node (ref "LED17") (pin "1-VDD") (pinfunction "VDD_1-VDD") (pintype "power_in"))
      (node (ref "LED18") (pin "1-VDD") (pinfunction "VDD_1-VDD") (pintype "power_in"))
      (node (ref "LED19") (pin "1-VDD") (pinfunction "VDD_1-VDD") (pintype "power_in"))
      (node (ref "LED2") (pin "1-VDD") (pinfunction "VDD_1-VDD") (pintype "power_in"))
      (node (ref "LED20") (pin "1-VDD") (pinfunction "VDD_1-VDD") (pintype "power_in"))
      (node (ref "LED21") (pin "1-VDD") (pinfunction "VDD_1-VDD") (pintype "power_in"))
      (node (ref "LED22") (pin "1-VDD") (pinfunction "VDD_1-VDD") (pintype "power_in"))
      (node (ref "LED23") (pin "1-VDD") (pinfunction "VDD_1-VDD") (pintype "power_in"))
      (node (ref "LED24") (pin "1-VDD") (pinfunction "VDD_1-VDD") (pintype "power_in"))
      (node (ref "LED25") (pin "1-VDD") (pinfunction "VDD_1-VDD") (pintype "power_in"))
      (node (ref "LED26") (pin "1-VDD") (pinfunction "VDD_1-VDD") (pintype "power_in"))
      (node (ref "LED27") (pin "1-VDD") (pinfunction "VDD_1-VDD") (pintype "power_in"))
      (node (ref "LED28") (pin "1-VDD") (pinfunction "VDD_1-VDD") (pintype "power_in"))
      (node (ref "LED29") (pin "1-VDD") (pinfunction "VDD_1-VDD") (pintype "power_in"))
      (node (ref "LED3") (pin "1-VDD") (pinfunction "VDD_1-VDD") (pintype "power_in"))
      (node (ref "LED30") (pin "1-VDD") (pinfunction "VDD_1-VDD") (pintype "power_in"))
      (node (ref "LED31") (pin "1-VDD") (pinfunction "VDD_1-VDD") (pintype "power_in"))
      (node (ref "LED32") (pin "1-VDD") (pinfunction "VDD_1-VDD") (pintype "power_in"))
      (node (ref "LED33") (pin "1-VDD") (pinfunction "VDD_1-VDD") (pintype "power_in"))
      (node (ref "LED34") (pin "1-VDD") (pinfunction "VDD_1-VDD") (pintype "power_in"))
      (node (ref "LED35") (pin "1-VDD") (pinfunction "VDD_1-VDD") (pintype "power_in"))
      (node (ref "LED36") (pin "1-VDD") (pinfunction "VDD_1-VDD") (pintype "power_in"))
      (node (ref "LED37") (pin "1-VDD") (pinfunction "VDD_1-VDD") (pintype "power_in"))
      (node (ref "LED38") (pin "1-VDD") (pinfunction "VDD_1-VDD") (pintype "power_in"))
      (node (ref "LED39") (pin "1-VDD") (pinfunction "VDD_1-VDD") (pintype "power_in"))
      (node (ref "LED4") (pin "1-VDD") (pinfunction "VDD_1-VDD") (pintype "power_in"))
      (node (ref "LED40") (pin "1-VDD") (pinfunction "VDD_1-VDD") (pintype "power_in"))
      (node (ref "LED41") (pin "1-VDD") (pinfunction "VDD_1-VDD") (pintype "power_in"))
      (node (ref "LED42") (pin "1-VDD") (pinfunction "VDD_1-VDD") (pintype "power_in"))
      (node (ref "LED43") (pin "1-VDD") (pinfunction "VDD_1-VDD") (pintype "power_in"))
      (node (ref "LED44") (pin "1-VDD") (pinfunction "VDD_1-VDD") (pintype "power_in"))
      (node (ref "LED45") (pin "1-VDD") (pinfunction "VDD_1-VDD") (pintype "power_in"))
      (node (ref "LED46") (pin "1-VDD") (pinfunction "VDD_1-VDD") (pintype "power_in"))
      (node (ref "LED47") (pin "1-VDD") (pinfunction "VDD_1-VDD") (pintype "power_in"))
      (node (ref "LED48") (pin "1-VDD") (pinfunction "VDD_1-VDD") (pintype "power_in"))
      (node (ref "LED49") (pin "1-VDD") (pinfunction "VDD_1-VDD") (pintype "power_in"))
      (node (ref "LED5") (pin "1-VDD") (pinfunction "VDD_1-VDD") (pintype "power_in"))
      (node (ref "LED50") (pin "1-VDD") (pinfunction "VDD_1-VDD") (pintype "power_in"))
      (node (ref "LED51") (pin "1-VDD") (pinfunction "VDD_1-VDD") (pintype "power_in"))
      (node (ref "LED52") (pin "1-VDD") (pinfunction "VDD_1-VDD") (pintype "power_in"))
      (node (ref "LED53") (pin "1-VDD") (pinfunction "VDD_1-VDD") (pintype "power_in"))
      (node (ref "LED54") (pin "1-VDD") (pinfunction "VDD_1-VDD") (pintype "power_in"))
      (node (ref "LED55") (pin "1-VDD") (pinfunction "VDD_1-VDD") (pintype "power_in"))
      (node (ref "LED56") (pin "1-VDD") (pinfunction "VDD_1-VDD") (pintype "power_in"))
      (node (ref "LED57") (pin "1-VDD") (pinfunction "VDD_1-VDD") (pintype "power_in"))
      (node (ref "LED58") (pin "1-VDD") (pinfunction "VDD_1-VDD") (pintype "power_in"))
      (node (ref "LED59") (pin "1-VDD") (pinfunction "VDD_1-VDD") (pintype "power_in"))
      (node (ref "LED6") (pin "1-VDD") (pinfunction "VDD_1-VDD") (pintype "power_in"))
      (node (ref "LED60") (pin "1-VDD") (pinfunction "VDD_1-VDD") (pintype "power_in"))
      (node (ref "LED61") (pin "1-VDD") (pinfunction "VDD_1-VDD") (pintype "power_in"))
      (node (ref "LED62") (pin "1-VDD") (pinfunction "VDD_1-VDD") (pintype "power_in"))
      (node (ref "LED63") (pin "1-VDD") (pinfunction "VDD_1-VDD") (pintype "power_in"))
      (node (ref "LED64") (pin "1-VDD") (pinfunction "VDD_1-VDD") (pintype "power_in"))
      (node (ref "LED65") (pin "1-VDD") (pinfunction "VDD_1-VDD") (pintype "power_in"))
      (node (ref "LED66") (pin "1-VDD") (pinfunction "VDD_1-VDD") (pintype "power_in"))
      (node (ref "LED67") (pin "1-VDD") (pinfunction "VDD_1-VDD") (pintype "power_in"))
      (node (ref "LED68") (pin "1-VDD") (pinfunction "VDD_1-VDD") (pintype "power_in"))
      (node (ref "LED69") (pin "1-VDD") (pinfunction "VDD_1-VDD") (pintype "power_in"))
      (node (ref "LED7") (pin "1-VDD") (pinfunction "VDD_1-VDD") (pintype "power_in"))
      (node (ref "LED70") (pin "1-VDD") (pinfunction "VDD_1-VDD") (pintype "power_in"))
      (node (ref "LED71") (pin "1-VDD") (pinfunction "VDD_1-VDD") (pintype "power_in"))
      (node (ref "LED72") (pin "1-VDD") (pinfunction "VDD_1-VDD") (pintype "power_in"))
      (node (ref "LED73") (pin "1-VDD") (pinfunction "VDD_1-VDD") (pintype "power_in"))
      (node (ref "LED74") (pin "1-VDD") (pinfunction "VDD_1-VDD") (pintype "power_in"))
      (node (ref "LED75") (pin "1-VDD") (pinfunction "VDD_1-VDD") (pintype "power_in"))
      (node (ref "LED76") (pin "1-VDD") (pinfunction "VDD_1-VDD") (pintype "power_in"))
      (node (ref "LED77") (pin "1-VDD") (pinfunction "VDD_1-VDD") (pintype "power_in"))
      (node (ref "LED78") (pin "1-VDD") (pinfunction "VDD_1-VDD") (pintype "power_in"))
      (node (ref "LED79") (pin "1-VDD") (pinfunction "VDD_1-VDD") (pintype "power_in"))
      (node (ref "LED8") (pin "1-VDD") (pinfunction "VDD_1-VDD") (pintype "power_in"))
      (node (ref "LED80") (pin "1-VDD") (pinfunction "VDD_1-VDD") (pintype "power_in"))
      (node (ref "LED81") (pin "1-VDD") (pinfunction "VDD_1-VDD") (pintype "power_in"))
      (node (ref "LED82") (pin "1-VDD") (pinfunction "VDD_1-VDD") (pintype "power_in"))
      (node (ref "LED83") (pin "1-VDD") (pinfunction "VDD_1-VDD") (pintype "power_in"))
      (node (ref "LED84") (pin "1-VDD") (pinfunction "VDD_1-VDD") (pintype "power_in"))
      (node (ref "LED85") (pin "1-VDD") (pinfunction "VDD_1-VDD") (pintype "power_in"))
      (node (ref "LED86") (pin "1-VDD") (pinfunction "VDD_1-VDD") (pintype "power_in"))
      (node (ref "LED87") (pin "1-VDD") (pinfunction "VDD_1-VDD") (pintype "power_in"))
      (node (ref "LED88") (pin "1-VDD") (pinfunction "VDD_1-VDD") (pintype "power_in"))
      (node (ref "LED89") (pin "1-VDD") (pinfunction "VDD_1-VDD") (pintype "power_in"))
      (node (ref "LED9") (pin "1-VDD") (pinfunction "VDD_1-VDD") (pintype "power_in"))
      (node (ref "LED90") (pin "1-VDD") (pinfunction "VDD_1-VDD") (pintype "power_in"))
      (node (ref "LED91") (pin "1-VDD") (pinfunction "VDD_1-VDD") (pintype "power_in"))
      (node (ref "LED92") (pin "1-VDD") (pinfunction "VDD_1-VDD") (pintype "power_in"))
      (node (ref "LED93") (pin "1-VDD") (pinfunction "VDD_1-VDD") (pintype "power_in"))
      (node (ref "LED94") (pin "1-VDD") (pinfunction "VDD_1-VDD") (pintype "power_in"))
      (node (ref "LED95") (pin "1-VDD") (pinfunction "VDD_1-VDD") (pintype "power_in"))
      (node (ref "LED96") (pin "1-VDD") (pinfunction "VDD_1-VDD") (pintype "power_in"))
      (node (ref "LED97") (pin "1-VDD") (pinfunction "VDD_1-VDD") (pintype "power_in"))
      (node (ref "LED98") (pin "1-VDD") (pinfunction "VDD_1-VDD") (pintype "power_in"))
      (node (ref "LED99") (pin "1-VDD") (pinfunction "VDD_1-VDD") (pintype "power_in"))
    )
  )
)
